# M225X.net
KiCad netlist of a schematic drawn in EAGLE
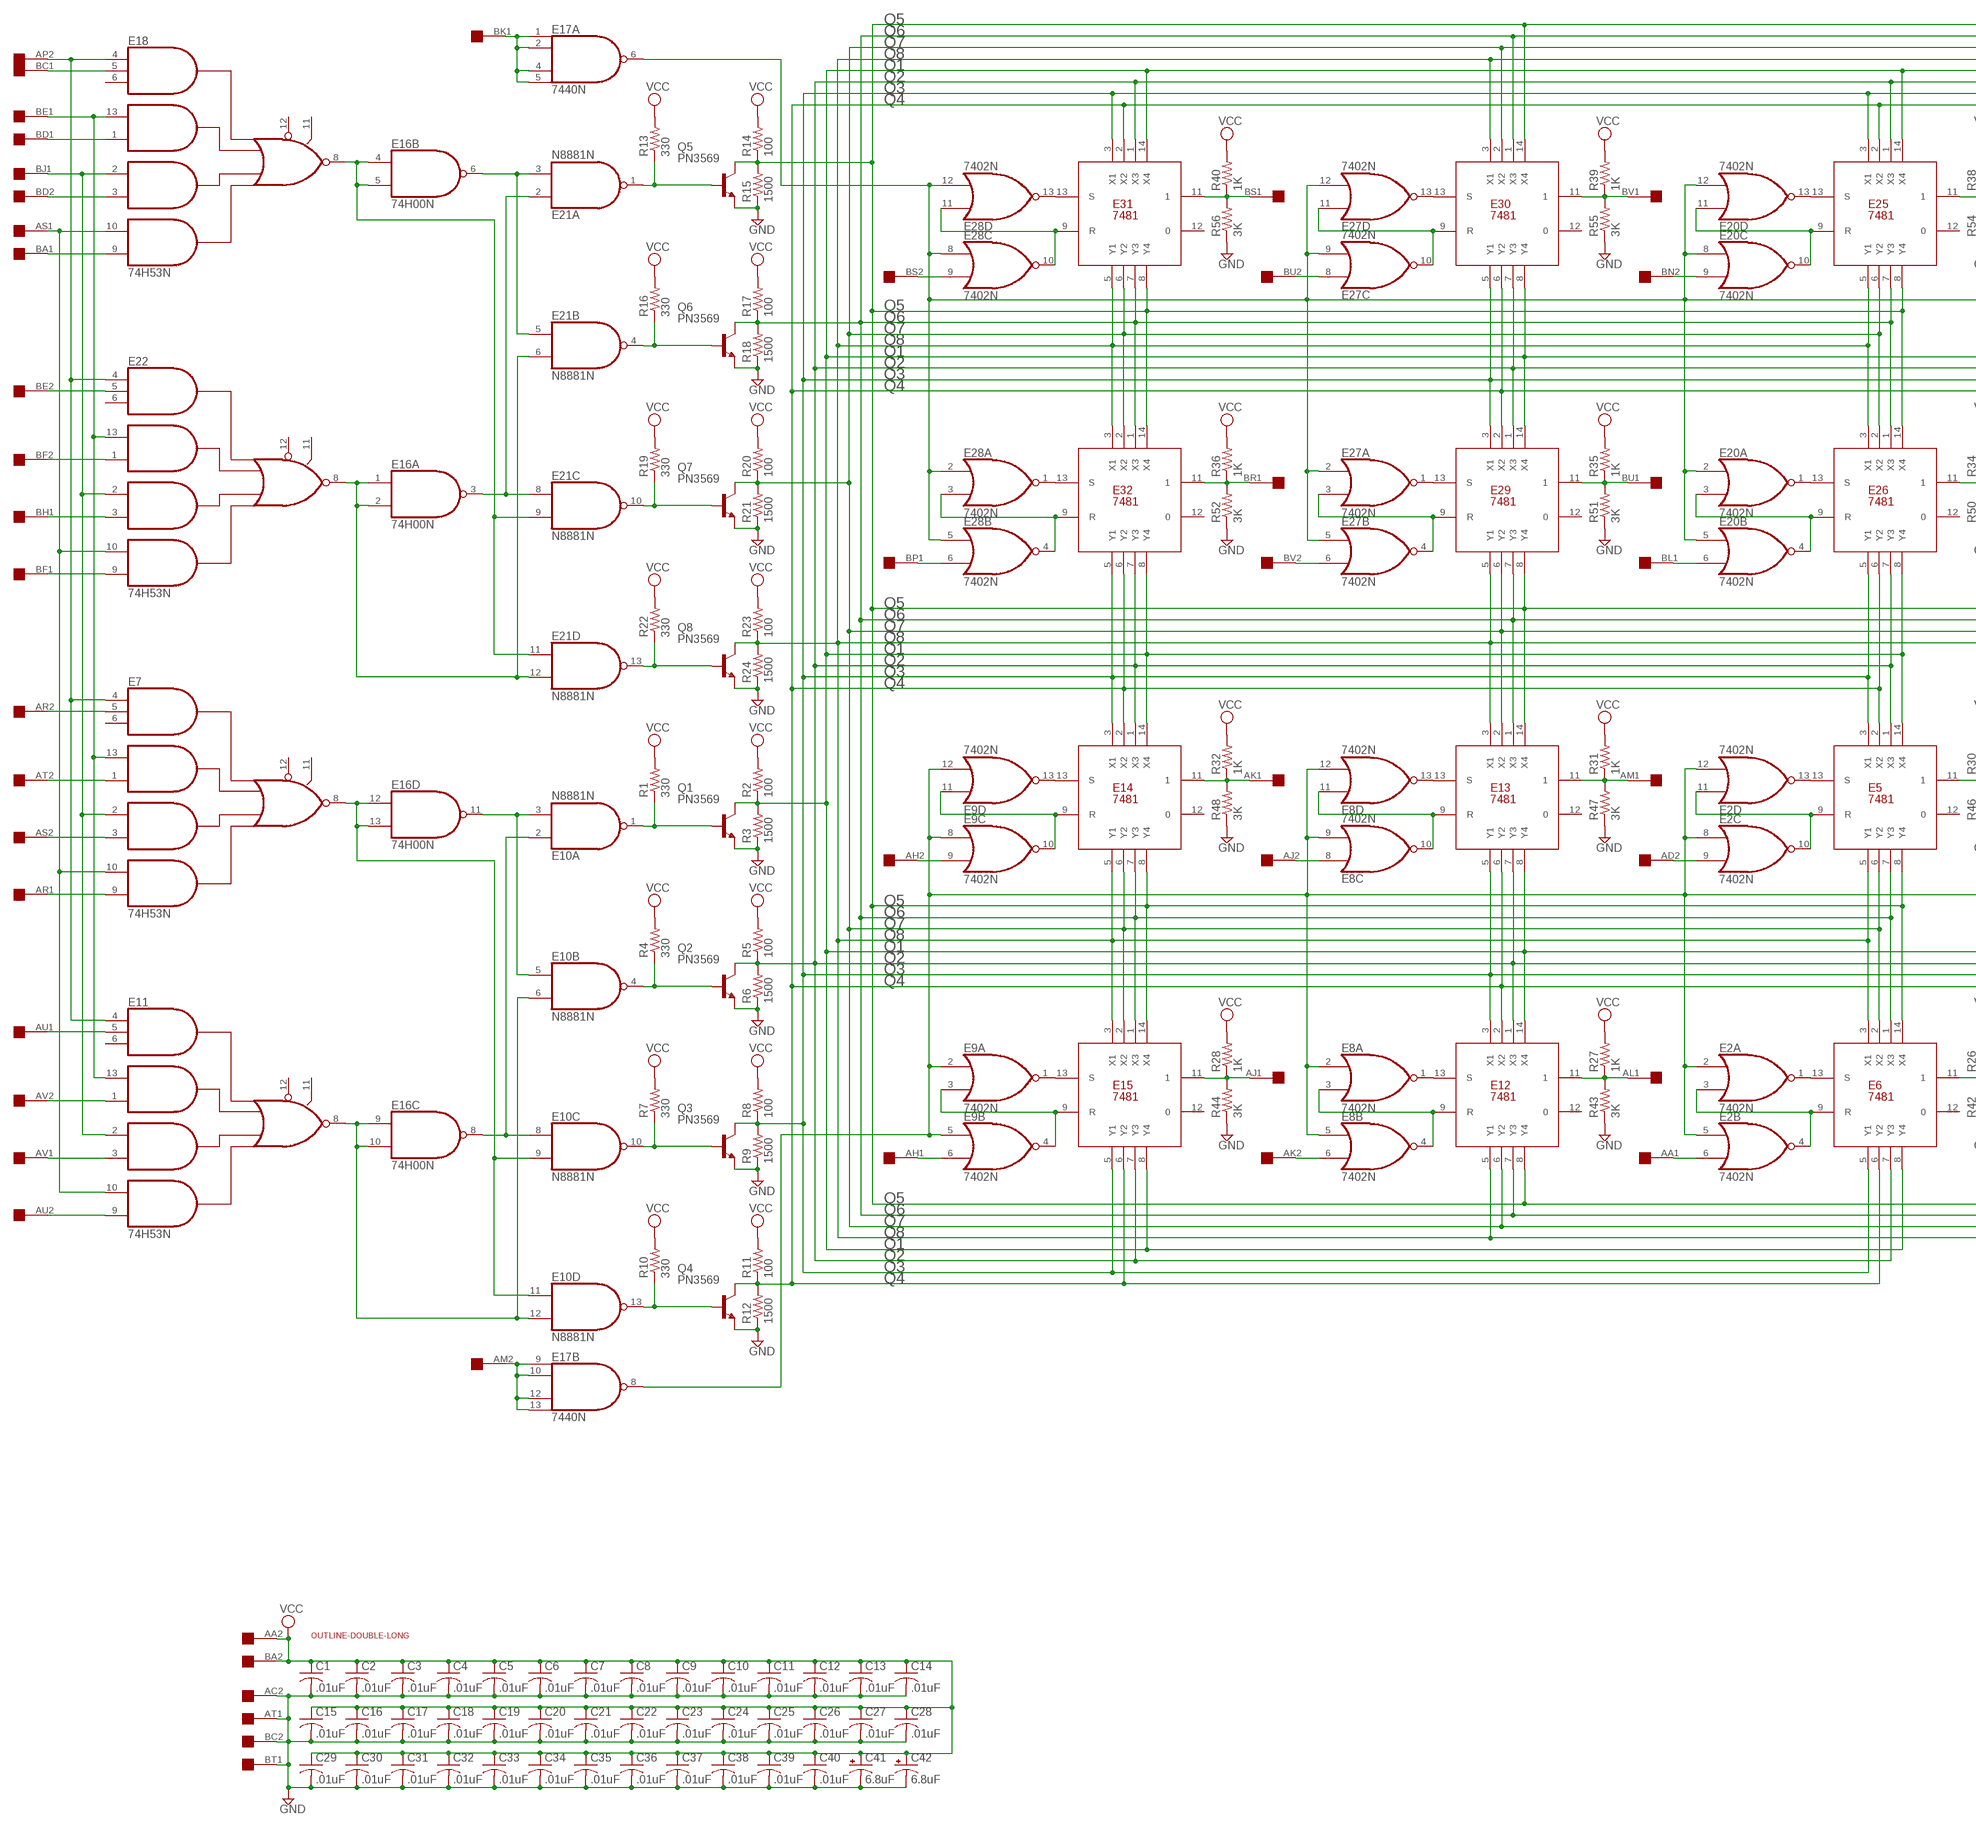
[diagram p0: schematic, sheet 1, part 1 of 2]
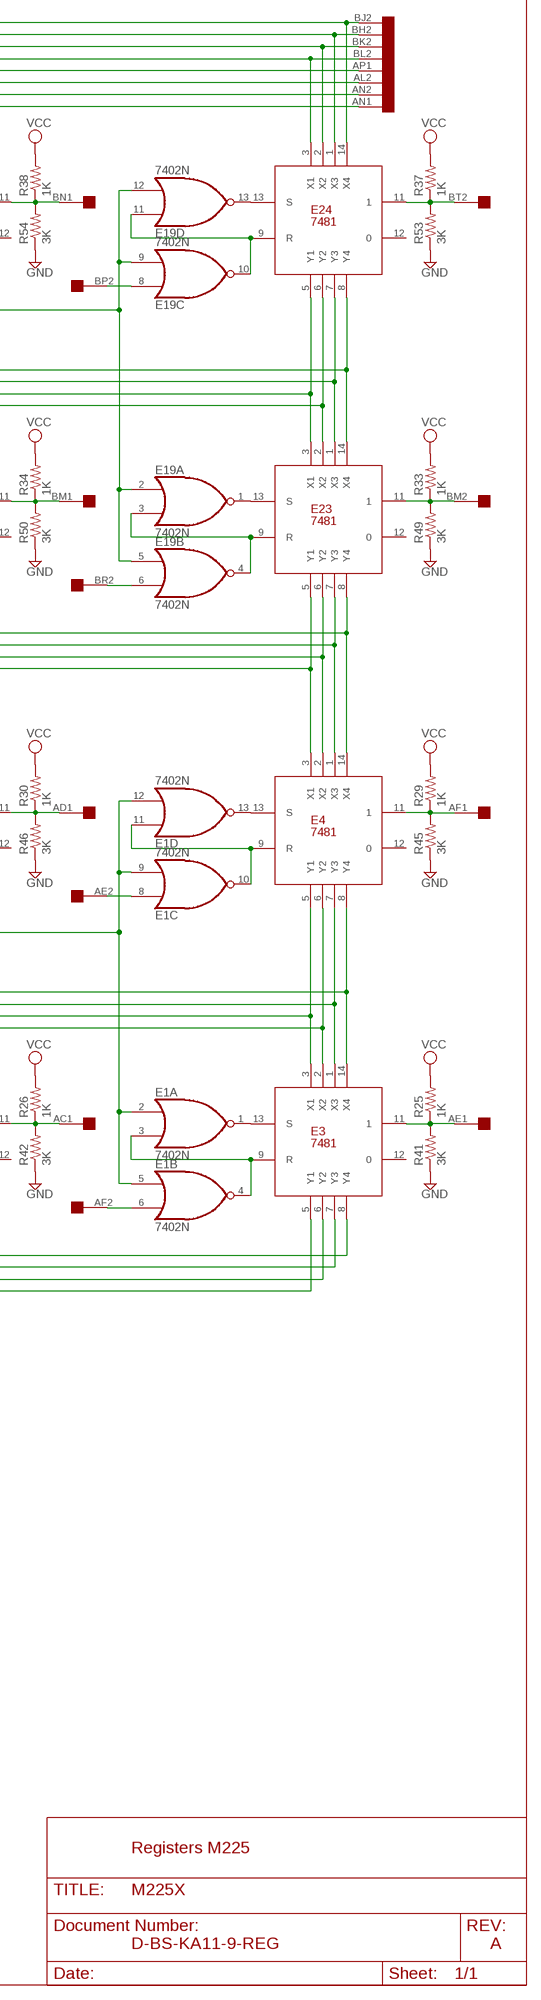
[diagram p1: schematic, sheet 1, part 2 of 2]

(export (version "E")
  (design (tool "Eeschema 10.0.6"))
  (components
    (comp (ref "C1")
      (value ".01uF")
      (footprint "eagle-import:C050-025X075")
      (libsource (lib "eagle-import") (part "C-US050-025X075"))
    )
    (comp (ref "C2")
      (value ".01uF")
      (footprint "eagle-import:C050-025X075")
      (libsource (lib "eagle-import") (part "C-US050-025X075"))
    )
    (comp (ref "C3")
      (value ".01uF")
      (footprint "eagle-import:C050-025X075")
      (libsource (lib "eagle-import") (part "C-US050-025X075"))
    )
    (comp (ref "C4")
      (value ".01uF")
      (footprint "eagle-import:C050-025X075")
      (libsource (lib "eagle-import") (part "C-US050-025X075"))
    )
    (comp (ref "C5")
      (value ".01uF")
      (footprint "eagle-import:C050-025X075")
      (libsource (lib "eagle-import") (part "C-US050-025X075"))
    )
    (comp (ref "C6")
      (value ".01uF")
      (footprint "eagle-import:C050-025X075")
      (libsource (lib "eagle-import") (part "C-US050-025X075"))
    )
    (comp (ref "C7")
      (value ".01uF")
      (footprint "eagle-import:C050-025X075")
      (libsource (lib "eagle-import") (part "C-US050-025X075"))
    )
    (comp (ref "C8")
      (value ".01uF")
      (footprint "eagle-import:C050-025X075")
      (libsource (lib "eagle-import") (part "C-US050-025X075"))
    )
    (comp (ref "C9")
      (value ".01uF")
      (footprint "eagle-import:C050-025X075")
      (libsource (lib "eagle-import") (part "C-US050-025X075"))
    )
    (comp (ref "C10")
      (value ".01uF")
      (footprint "eagle-import:C050-025X075")
      (libsource (lib "eagle-import") (part "C-US050-025X075"))
    )
    (comp (ref "C11")
      (value ".01uF")
      (footprint "eagle-import:C050-025X075")
      (libsource (lib "eagle-import") (part "C-US050-025X075"))
    )
    (comp (ref "C12")
      (value ".01uF")
      (footprint "eagle-import:C050-025X075")
      (libsource (lib "eagle-import") (part "C-US050-025X075"))
    )
    (comp (ref "C13")
      (value ".01uF")
      (footprint "eagle-import:C050-025X075")
      (libsource (lib "eagle-import") (part "C-US050-025X075"))
    )
    (comp (ref "C14")
      (value ".01uF")
      (footprint "eagle-import:C050-025X075")
      (libsource (lib "eagle-import") (part "C-US050-025X075"))
    )
    (comp (ref "C15")
      (value ".01uF")
      (footprint "eagle-import:C050-025X075")
      (libsource (lib "eagle-import") (part "C-US050-025X075"))
    )
    (comp (ref "C16")
      (value ".01uF")
      (footprint "eagle-import:C050-025X075")
      (libsource (lib "eagle-import") (part "C-US050-025X075"))
    )
    (comp (ref "C17")
      (value ".01uF")
      (footprint "eagle-import:C050-025X075")
      (libsource (lib "eagle-import") (part "C-US050-025X075"))
    )
    (comp (ref "C18")
      (value ".01uF")
      (footprint "eagle-import:C050-025X075")
      (libsource (lib "eagle-import") (part "C-US050-025X075"))
    )
    (comp (ref "C19")
      (value ".01uF")
      (footprint "eagle-import:C050-025X075")
      (libsource (lib "eagle-import") (part "C-US050-025X075"))
    )
    (comp (ref "C20")
      (value ".01uF")
      (footprint "eagle-import:C050-025X075")
      (libsource (lib "eagle-import") (part "C-US050-025X075"))
    )
    (comp (ref "C21")
      (value ".01uF")
      (footprint "eagle-import:C050-025X075")
      (libsource (lib "eagle-import") (part "C-US050-025X075"))
    )
    (comp (ref "C22")
      (value ".01uF")
      (footprint "eagle-import:C050-025X075")
      (libsource (lib "eagle-import") (part "C-US050-025X075"))
    )
    (comp (ref "C23")
      (value ".01uF")
      (footprint "eagle-import:C050-025X075")
      (libsource (lib "eagle-import") (part "C-US050-025X075"))
    )
    (comp (ref "C24")
      (value ".01uF")
      (footprint "eagle-import:C050-025X075")
      (libsource (lib "eagle-import") (part "C-US050-025X075"))
    )
    (comp (ref "C25")
      (value ".01uF")
      (footprint "eagle-import:C050-025X075")
      (libsource (lib "eagle-import") (part "C-US050-025X075"))
    )
    (comp (ref "C26")
      (value ".01uF")
      (footprint "eagle-import:C050-025X075")
      (libsource (lib "eagle-import") (part "C-US050-025X075"))
    )
    (comp (ref "C27")
      (value ".01uF")
      (footprint "eagle-import:C050-025X075")
      (libsource (lib "eagle-import") (part "C-US050-025X075"))
    )
    (comp (ref "C28")
      (value ".01uF")
      (footprint "eagle-import:C050-025X075")
      (libsource (lib "eagle-import") (part "C-US050-025X075"))
    )
    (comp (ref "C29")
      (value ".01uF")
      (footprint "eagle-import:C050-025X075")
      (libsource (lib "eagle-import") (part "C-US050-025X075"))
    )
    (comp (ref "C30")
      (value ".01uF")
      (footprint "eagle-import:C050-025X075")
      (libsource (lib "eagle-import") (part "C-US050-025X075"))
    )
    (comp (ref "C31")
      (value ".01uF")
      (footprint "eagle-import:C050-025X075")
      (libsource (lib "eagle-import") (part "C-US050-025X075"))
    )
    (comp (ref "C32")
      (value ".01uF")
      (footprint "eagle-import:C050-025X075")
      (libsource (lib "eagle-import") (part "C-US050-025X075"))
    )
    (comp (ref "C33")
      (value ".01uF")
      (footprint "eagle-import:C050-025X075")
      (libsource (lib "eagle-import") (part "C-US050-025X075"))
    )
    (comp (ref "C34")
      (value ".01uF")
      (footprint "eagle-import:C050-025X075")
      (libsource (lib "eagle-import") (part "C-US050-025X075"))
    )
    (comp (ref "C35")
      (value ".01uF")
      (footprint "eagle-import:C050-025X075")
      (libsource (lib "eagle-import") (part "C-US050-025X075"))
    )
    (comp (ref "C36")
      (value ".01uF")
      (footprint "eagle-import:C050-025X075")
      (libsource (lib "eagle-import") (part "C-US050-025X075"))
    )
    (comp (ref "C37")
      (value ".01uF")
      (footprint "eagle-import:C050-025X075")
      (libsource (lib "eagle-import") (part "C-US050-025X075"))
    )
    (comp (ref "C38")
      (value ".01uF")
      (footprint "eagle-import:C050-025X075")
      (libsource (lib "eagle-import") (part "C-US050-025X075"))
    )
    (comp (ref "C39")
      (value ".01uF")
      (footprint "eagle-import:C050-025X075")
      (libsource (lib "eagle-import") (part "C-US050-025X075"))
    )
    (comp (ref "C40")
      (value ".01uF")
      (footprint "eagle-import:C050-025X075")
      (libsource (lib "eagle-import") (part "C-US050-025X075"))
    )
    (comp (ref "C41")
      (value "6.8uF")
      (footprint "eagle-import:E12-8")
      (libsource (lib "eagle-import") (part "CPOL-USE20-8AXIAL"))
    )
    (comp (ref "C42")
      (value "6.8uF")
      (footprint "eagle-import:E12-8")
      (libsource (lib "eagle-import") (part "CPOL-USE20-8AXIAL"))
    )
    (comp (ref "E1")
      (value "7402N")
      (footprint "eagle-import:DIL14")
      (libsource (lib "eagle-import") (part "7402N"))
    )
    (comp (ref "E2")
      (value "7402N")
      (footprint "eagle-import:DIL14")
      (libsource (lib "eagle-import") (part "7402N"))
    )
    (comp (ref "E3")
      (value "7481")
      (footprint "eagle-import:DIL14")
      (libsource (lib "eagle-import") (part "7481"))
    )
    (comp (ref "E4")
      (value "7481")
      (footprint "eagle-import:DIL14")
      (libsource (lib "eagle-import") (part "7481"))
    )
    (comp (ref "E5")
      (value "7481")
      (footprint "eagle-import:DIL14")
      (libsource (lib "eagle-import") (part "7481"))
    )
    (comp (ref "E6")
      (value "7481")
      (footprint "eagle-import:DIL14")
      (libsource (lib "eagle-import") (part "7481"))
    )
    (comp (ref "E7")
      (value "74H53N")
      (footprint "eagle-import:DIL14")
      (libsource (lib "eagle-import") (part "74H53N"))
    )
    (comp (ref "E8")
      (value "7402N")
      (footprint "eagle-import:DIL14")
      (libsource (lib "eagle-import") (part "7402N"))
    )
    (comp (ref "E9")
      (value "7402N")
      (footprint "eagle-import:DIL14")
      (libsource (lib "eagle-import") (part "7402N"))
    )
    (comp (ref "E10")
      (value "N8881N")
      (footprint "eagle-import:DIL14")
      (libsource (lib "eagle-import") (part "N8881N"))
    )
    (comp (ref "E11")
      (value "74H53N")
      (footprint "eagle-import:DIL14")
      (libsource (lib "eagle-import") (part "74H53N"))
    )
    (comp (ref "E12")
      (value "7481")
      (footprint "eagle-import:DIL14")
      (libsource (lib "eagle-import") (part "7481"))
    )
    (comp (ref "E13")
      (value "7481")
      (footprint "eagle-import:DIL14")
      (libsource (lib "eagle-import") (part "7481"))
    )
    (comp (ref "E14")
      (value "7481")
      (footprint "eagle-import:DIL14")
      (libsource (lib "eagle-import") (part "7481"))
    )
    (comp (ref "E15")
      (value "7481")
      (footprint "eagle-import:DIL14")
      (libsource (lib "eagle-import") (part "7481"))
    )
    (comp (ref "E16")
      (value "74H00N")
      (footprint "eagle-import:DIL14")
      (libsource (lib "eagle-import") (part "7400NS"))
    )
    (comp (ref "E17")
      (value "7440N")
      (footprint "eagle-import:DIL14")
      (libsource (lib "eagle-import") (part "7440N"))
    )
    (comp (ref "E18")
      (value "74H53N")
      (footprint "eagle-import:DIL14")
      (libsource (lib "eagle-import") (part "74H53N"))
    )
    (comp (ref "E19")
      (value "7402N")
      (footprint "eagle-import:DIL14")
      (libsource (lib "eagle-import") (part "7402N"))
    )
    (comp (ref "E20")
      (value "7402N")
      (footprint "eagle-import:DIL14")
      (libsource (lib "eagle-import") (part "7402N"))
    )
    (comp (ref "E21")
      (value "N8881N")
      (footprint "eagle-import:DIL14")
      (libsource (lib "eagle-import") (part "N8881N"))
    )
    (comp (ref "E22")
      (value "74H53N")
      (footprint "eagle-import:DIL14")
      (libsource (lib "eagle-import") (part "74H53N"))
    )
    (comp (ref "E23")
      (value "7481")
      (footprint "eagle-import:DIL14")
      (libsource (lib "eagle-import") (part "7481"))
    )
    (comp (ref "E24")
      (value "7481")
      (footprint "eagle-import:DIL14")
      (libsource (lib "eagle-import") (part "7481"))
    )
    (comp (ref "E25")
      (value "7481")
      (footprint "eagle-import:DIL14")
      (libsource (lib "eagle-import") (part "7481"))
    )
    (comp (ref "E26")
      (value "7481")
      (footprint "eagle-import:DIL14")
      (libsource (lib "eagle-import") (part "7481"))
    )
    (comp (ref "E27")
      (value "7402N")
      (footprint "eagle-import:DIL14")
      (libsource (lib "eagle-import") (part "7402N"))
    )
    (comp (ref "E28")
      (value "7402N")
      (footprint "eagle-import:DIL14")
      (libsource (lib "eagle-import") (part "7402N"))
    )
    (comp (ref "E29")
      (value "7481")
      (footprint "eagle-import:DIL14")
      (libsource (lib "eagle-import") (part "7481"))
    )
    (comp (ref "E30")
      (value "7481")
      (footprint "eagle-import:DIL14")
      (libsource (lib "eagle-import") (part "7481"))
    )
    (comp (ref "E31")
      (value "7481")
      (footprint "eagle-import:DIL14")
      (libsource (lib "eagle-import") (part "7481"))
    )
    (comp (ref "E32")
      (value "7481")
      (footprint "eagle-import:DIL14")
      (libsource (lib "eagle-import") (part "7481"))
    )
    (comp (ref "Q1")
      (value "PN3569")
      (footprint "eagle-import:TO5")
      (libsource (lib "eagle-import") (part "-NPN-TO5"))
    )
    (comp (ref "Q2")
      (value "PN3569")
      (footprint "eagle-import:TO5")
      (libsource (lib "eagle-import") (part "-NPN-TO5"))
    )
    (comp (ref "Q3")
      (value "PN3569")
      (footprint "eagle-import:TO5")
      (libsource (lib "eagle-import") (part "-NPN-TO5"))
    )
    (comp (ref "Q4")
      (value "PN3569")
      (footprint "eagle-import:TO5")
      (libsource (lib "eagle-import") (part "-NPN-TO5"))
    )
    (comp (ref "Q5")
      (value "PN3569")
      (footprint "eagle-import:TO5")
      (libsource (lib "eagle-import") (part "-NPN-TO5"))
    )
    (comp (ref "Q6")
      (value "PN3569")
      (footprint "eagle-import:TO5")
      (libsource (lib "eagle-import") (part "-NPN-TO5"))
    )
    (comp (ref "Q7")
      (value "PN3569")
      (footprint "eagle-import:TO5")
      (libsource (lib "eagle-import") (part "-NPN-TO5"))
    )
    (comp (ref "Q8")
      (value "PN3569")
      (footprint "eagle-import:TO5")
      (libsource (lib "eagle-import") (part "-NPN-TO5"))
    )
    (comp (ref "R1")
      (value "330")
      (footprint "eagle-import:0207_10")
      (libsource (lib "eagle-import") (part "R-US_0207/10"))
    )
    (comp (ref "R2")
      (value "100")
      (footprint "eagle-import:0207_10")
      (libsource (lib "eagle-import") (part "R-US_0207/10"))
    )
    (comp (ref "R3")
      (value "1500")
      (footprint "eagle-import:0207_10")
      (libsource (lib "eagle-import") (part "R-US_0207/10"))
    )
    (comp (ref "R4")
      (value "330")
      (footprint "eagle-import:0207_10")
      (libsource (lib "eagle-import") (part "R-US_0207/10"))
    )
    (comp (ref "R5")
      (value "100")
      (footprint "eagle-import:0207_10")
      (libsource (lib "eagle-import") (part "R-US_0207/10"))
    )
    (comp (ref "R6")
      (value "1500")
      (footprint "eagle-import:0207_10")
      (libsource (lib "eagle-import") (part "R-US_0207/10"))
    )
    (comp (ref "R7")
      (value "330")
      (footprint "eagle-import:0207_10")
      (libsource (lib "eagle-import") (part "R-US_0207/10"))
    )
    (comp (ref "R8")
      (value "100")
      (footprint "eagle-import:0207_10")
      (libsource (lib "eagle-import") (part "R-US_0207/10"))
    )
    (comp (ref "R9")
      (value "1500")
      (footprint "eagle-import:0207_10")
      (libsource (lib "eagle-import") (part "R-US_0207/10"))
    )
    (comp (ref "R10")
      (value "330")
      (footprint "eagle-import:0207_10")
      (libsource (lib "eagle-import") (part "R-US_0207/10"))
    )
    (comp (ref "R11")
      (value "100")
      (footprint "eagle-import:0207_10")
      (libsource (lib "eagle-import") (part "R-US_0207/10"))
    )
    (comp (ref "R12")
      (value "1500")
      (footprint "eagle-import:0207_10")
      (libsource (lib "eagle-import") (part "R-US_0207/10"))
    )
    (comp (ref "R13")
      (value "330")
      (footprint "eagle-import:0207_10")
      (libsource (lib "eagle-import") (part "R-US_0207/10"))
    )
    (comp (ref "R14")
      (value "100")
      (footprint "eagle-import:0207_10")
      (libsource (lib "eagle-import") (part "R-US_0207/10"))
    )
    (comp (ref "R15")
      (value "1500")
      (footprint "eagle-import:0207_10")
      (libsource (lib "eagle-import") (part "R-US_0207/10"))
    )
    (comp (ref "R16")
      (value "330")
      (footprint "eagle-import:0207_10")
      (libsource (lib "eagle-import") (part "R-US_0207/10"))
    )
    (comp (ref "R17")
      (value "100")
      (footprint "eagle-import:0207_10")
      (libsource (lib "eagle-import") (part "R-US_0207/10"))
    )
    (comp (ref "R18")
      (value "1500")
      (footprint "eagle-import:0207_10")
      (libsource (lib "eagle-import") (part "R-US_0207/10"))
    )
    (comp (ref "R19")
      (value "330")
      (footprint "eagle-import:0207_10")
      (libsource (lib "eagle-import") (part "R-US_0207/10"))
    )
    (comp (ref "R20")
      (value "100")
      (footprint "eagle-import:0207_10")
      (libsource (lib "eagle-import") (part "R-US_0207/10"))
    )
    (comp (ref "R21")
      (value "1500")
      (footprint "eagle-import:0207_10")
      (libsource (lib "eagle-import") (part "R-US_0207/10"))
    )
    (comp (ref "R22")
      (value "330")
      (footprint "eagle-import:0207_10")
      (libsource (lib "eagle-import") (part "R-US_0207/10"))
    )
    (comp (ref "R23")
      (value "100")
      (footprint "eagle-import:0207_10")
      (libsource (lib "eagle-import") (part "R-US_0207/10"))
    )
    (comp (ref "R24")
      (value "1500")
      (footprint "eagle-import:0207_10")
      (libsource (lib "eagle-import") (part "R-US_0207/10"))
    )
    (comp (ref "R25")
      (value "1K")
      (footprint "eagle-import:0207_10")
      (libsource (lib "eagle-import") (part "R-US_0207/10"))
    )
    (comp (ref "R26")
      (value "1K")
      (footprint "eagle-import:0207_10")
      (libsource (lib "eagle-import") (part "R-US_0207/10"))
    )
    (comp (ref "R27")
      (value "1K")
      (footprint "eagle-import:0207_10")
      (libsource (lib "eagle-import") (part "R-US_0207/10"))
    )
    (comp (ref "R28")
      (value "1K")
      (footprint "eagle-import:0207_10")
      (libsource (lib "eagle-import") (part "R-US_0207/10"))
    )
    (comp (ref "R29")
      (value "1K")
      (footprint "eagle-import:0207_10")
      (libsource (lib "eagle-import") (part "R-US_0207/10"))
    )
    (comp (ref "R30")
      (value "1K")
      (footprint "eagle-import:0207_10")
      (libsource (lib "eagle-import") (part "R-US_0207/10"))
    )
    (comp (ref "R31")
      (value "1K")
      (footprint "eagle-import:0207_10")
      (libsource (lib "eagle-import") (part "R-US_0207/10"))
    )
    (comp (ref "R32")
      (value "1K")
      (footprint "eagle-import:0207_10")
      (libsource (lib "eagle-import") (part "R-US_0207/10"))
    )
    (comp (ref "R33")
      (value "1K")
      (footprint "eagle-import:0207_10")
      (libsource (lib "eagle-import") (part "R-US_0207/10"))
    )
    (comp (ref "R34")
      (value "1K")
      (footprint "eagle-import:0207_10")
      (libsource (lib "eagle-import") (part "R-US_0207/10"))
    )
    (comp (ref "R35")
      (value "1K")
      (footprint "eagle-import:0207_10")
      (libsource (lib "eagle-import") (part "R-US_0207/10"))
    )
    (comp (ref "R36")
      (value "1K")
      (footprint "eagle-import:0207_10")
      (libsource (lib "eagle-import") (part "R-US_0207/10"))
    )
    (comp (ref "R37")
      (value "1K")
      (footprint "eagle-import:0207_10")
      (libsource (lib "eagle-import") (part "R-US_0207/10"))
    )
    (comp (ref "R38")
      (value "1K")
      (footprint "eagle-import:0207_10")
      (libsource (lib "eagle-import") (part "R-US_0207/10"))
    )
    (comp (ref "R39")
      (value "1K")
      (footprint "eagle-import:0207_10")
      (libsource (lib "eagle-import") (part "R-US_0207/10"))
    )
    (comp (ref "R40")
      (value "1K")
      (footprint "eagle-import:0207_10")
      (libsource (lib "eagle-import") (part "R-US_0207/10"))
    )
    (comp (ref "R41")
      (value "3K")
      (footprint "eagle-import:0207_10")
      (libsource (lib "eagle-import") (part "R-US_0207/10"))
    )
    (comp (ref "R42")
      (value "3K")
      (footprint "eagle-import:0207_10")
      (libsource (lib "eagle-import") (part "R-US_0207/10"))
    )
    (comp (ref "R43")
      (value "3K")
      (footprint "eagle-import:0207_10")
      (libsource (lib "eagle-import") (part "R-US_0207/10"))
    )
    (comp (ref "R44")
      (value "3K")
      (footprint "eagle-import:0207_10")
      (libsource (lib "eagle-import") (part "R-US_0207/10"))
    )
    (comp (ref "R45")
      (value "3K")
      (footprint "eagle-import:0207_10")
      (libsource (lib "eagle-import") (part "R-US_0207/10"))
    )
    (comp (ref "R46")
      (value "3K")
      (footprint "eagle-import:0207_10")
      (libsource (lib "eagle-import") (part "R-US_0207/10"))
    )
    (comp (ref "R47")
      (value "3K")
      (footprint "eagle-import:0207_10")
      (libsource (lib "eagle-import") (part "R-US_0207/10"))
    )
    (comp (ref "R48")
      (value "3K")
      (footprint "eagle-import:0207_10")
      (libsource (lib "eagle-import") (part "R-US_0207/10"))
    )
    (comp (ref "R49")
      (value "3K")
      (footprint "eagle-import:0207_10")
      (libsource (lib "eagle-import") (part "R-US_0207/10"))
    )
    (comp (ref "R50")
      (value "3K")
      (footprint "eagle-import:0207_10")
      (libsource (lib "eagle-import") (part "R-US_0207/10"))
    )
    (comp (ref "R51")
      (value "3K")
      (footprint "eagle-import:0207_10")
      (libsource (lib "eagle-import") (part "R-US_0207/10"))
    )
    (comp (ref "R52")
      (value "3K")
      (footprint "eagle-import:0207_10")
      (libsource (lib "eagle-import") (part "R-US_0207/10"))
    )
    (comp (ref "R53")
      (value "3K")
      (footprint "eagle-import:0207_10")
      (libsource (lib "eagle-import") (part "R-US_0207/10"))
    )
    (comp (ref "R54")
      (value "3K")
      (footprint "eagle-import:0207_10")
      (libsource (lib "eagle-import") (part "R-US_0207/10"))
    )
    (comp (ref "R55")
      (value "3K")
      (footprint "eagle-import:0207_10")
      (libsource (lib "eagle-import") (part "R-US_0207/10"))
    )
    (comp (ref "R56")
      (value "3K")
      (footprint "eagle-import:0207_10")
      (libsource (lib "eagle-import") (part "R-US_0207/10"))
    )
    (comp (ref "U$1")
      (value "OUTLINE-DOUBLE-LONG")
      (footprint "eagle-import:DOUBLE-LONG")
      (libsource (lib "eagle-import") (part "OUTLINE-DOUBLE-LONG"))
    )
    (comp (ref "U$3")
      (value "DOUBLE")
      (footprint "eagle-import:EDGE-CON4")
      (libsource (lib "eagle-import") (part "DOUBLE"))
    )
  )
  (nets
    (net (code "1") (name "/Q1") (class "Default")
      (node (ref "E12") (pin "14") (pinfunction "X4_14") (pintype "input"))
      (node (ref "E13") (pin "8") (pinfunction "Y4_8") (pintype "input"))
      (node (ref "E14") (pin "14") (pinfunction "X4_14") (pintype "input"))
      (node (ref "E15") (pin "8") (pinfunction "Y4_8") (pintype "input"))
      (node (ref "E23") (pin "14") (pinfunction "X4_14") (pintype "input"))
      (node (ref "E24") (pin "8") (pinfunction "Y4_8") (pintype "input"))
      (node (ref "E25") (pin "14") (pinfunction "X4_14") (pintype "input"))
      (node (ref "E26") (pin "8") (pinfunction "Y4_8") (pintype "input"))
      (node (ref "E29") (pin "14") (pinfunction "X4_14") (pintype "input"))
      (node (ref "E3") (pin "14") (pinfunction "X4_14") (pintype "input"))
      (node (ref "E30") (pin "8") (pinfunction "Y4_8") (pintype "input"))
      (node (ref "E31") (pin "14") (pinfunction "X4_14") (pintype "input"))
      (node (ref "E32") (pin "8") (pinfunction "Y4_8") (pintype "input"))
      (node (ref "E4") (pin "8") (pinfunction "Y4_8") (pintype "input"))
      (node (ref "E5") (pin "14") (pinfunction "X4_14") (pintype "input"))
      (node (ref "E6") (pin "8") (pinfunction "Y4_8") (pintype "input"))
      (node (ref "Q1") (pin "3") (pinfunction "C_3") (pintype "passive"))
      (node (ref "R2") (pin "1") (pinfunction "1_1") (pintype "passive"))
      (node (ref "R3") (pin "2") (pinfunction "2_2") (pintype "passive"))
      (node (ref "U$3") (pin "AP1") (pinfunction "1_AP1") (pintype "bidirectional"))
    )
    (net (code "2") (name "/Q2") (class "Default")
      (node (ref "E12") (pin "1") (pinfunction "X3_1") (pintype "input"))
      (node (ref "E13") (pin "7") (pinfunction "Y3_7") (pintype "input"))
      (node (ref "E14") (pin "1") (pinfunction "X3_1") (pintype "input"))
      (node (ref "E15") (pin "7") (pinfunction "Y3_7") (pintype "input"))
      (node (ref "E23") (pin "1") (pinfunction "X3_1") (pintype "input"))
      (node (ref "E24") (pin "7") (pinfunction "Y3_7") (pintype "input"))
      (node (ref "E25") (pin "1") (pinfunction "X3_1") (pintype "input"))
      (node (ref "E26") (pin "7") (pinfunction "Y3_7") (pintype "input"))
      (node (ref "E29") (pin "1") (pinfunction "X3_1") (pintype "input"))
      (node (ref "E3") (pin "1") (pinfunction "X3_1") (pintype "input"))
      (node (ref "E30") (pin "7") (pinfunction "Y3_7") (pintype "input"))
      (node (ref "E31") (pin "1") (pinfunction "X3_1") (pintype "input"))
      (node (ref "E32") (pin "7") (pinfunction "Y3_7") (pintype "input"))
      (node (ref "E4") (pin "7") (pinfunction "Y3_7") (pintype "input"))
      (node (ref "E5") (pin "1") (pinfunction "X3_1") (pintype "input"))
      (node (ref "E6") (pin "7") (pinfunction "Y3_7") (pintype "input"))
      (node (ref "Q2") (pin "3") (pinfunction "C_3") (pintype "passive"))
      (node (ref "R5") (pin "1") (pinfunction "1_1") (pintype "passive"))
      (node (ref "R6") (pin "2") (pinfunction "2_2") (pintype "passive"))
      (node (ref "U$3") (pin "AL2") (pinfunction "1_AL2") (pintype "bidirectional"))
    )
    (net (code "3") (name "/Q3") (class "Default")
      (node (ref "E12") (pin "3") (pinfunction "X1_3") (pintype "input"))
      (node (ref "E13") (pin "5") (pinfunction "Y1_5") (pintype "input"))
      (node (ref "E14") (pin "3") (pinfunction "X1_3") (pintype "input"))
      (node (ref "E15") (pin "5") (pinfunction "Y1_5") (pintype "input"))
      (node (ref "E23") (pin "3") (pinfunction "X1_3") (pintype "input"))
      (node (ref "E24") (pin "5") (pinfunction "Y1_5") (pintype "input"))
      (node (ref "E25") (pin "3") (pinfunction "X1_3") (pintype "input"))
      (node (ref "E26") (pin "5") (pinfunction "Y1_5") (pintype "input"))
      (node (ref "E29") (pin "3") (pinfunction "X1_3") (pintype "input"))
      (node (ref "E3") (pin "3") (pinfunction "X1_3") (pintype "input"))
      (node (ref "E30") (pin "5") (pinfunction "Y1_5") (pintype "input"))
      (node (ref "E31") (pin "3") (pinfunction "X1_3") (pintype "input"))
      (node (ref "E32") (pin "5") (pinfunction "Y1_5") (pintype "input"))
      (node (ref "E4") (pin "5") (pinfunction "Y1_5") (pintype "input"))
      (node (ref "E5") (pin "3") (pinfunction "X1_3") (pintype "input"))
      (node (ref "E6") (pin "5") (pinfunction "Y1_5") (pintype "input"))
      (node (ref "Q3") (pin "3") (pinfunction "C_3") (pintype "passive"))
      (node (ref "R8") (pin "1") (pinfunction "1_1") (pintype "passive"))
      (node (ref "R9") (pin "2") (pinfunction "2_2") (pintype "passive"))
      (node (ref "U$3") (pin "AN2") (pinfunction "1_AN2") (pintype "bidirectional"))
    )
    (net (code "4") (name "/Q4") (class "Default")
      (node (ref "E12") (pin "2") (pinfunction "X2_2") (pintype "input"))
      (node (ref "E13") (pin "6") (pinfunction "Y2_6") (pintype "input"))
      (node (ref "E14") (pin "2") (pinfunction "X2_2") (pintype "input"))
      (node (ref "E15") (pin "6") (pinfunction "Y2_6") (pintype "input"))
      (node (ref "E23") (pin "2") (pinfunction "X2_2") (pintype "input"))
      (node (ref "E24") (pin "6") (pinfunction "Y2_6") (pintype "input"))
      (node (ref "E25") (pin "2") (pinfunction "X2_2") (pintype "input"))
      (node (ref "E26") (pin "6") (pinfunction "Y2_6") (pintype "input"))
      (node (ref "E29") (pin "2") (pinfunction "X2_2") (pintype "input"))
      (node (ref "E3") (pin "2") (pinfunction "X2_2") (pintype "input"))
      (node (ref "E30") (pin "6") (pinfunction "Y2_6") (pintype "input"))
      (node (ref "E31") (pin "2") (pinfunction "X2_2") (pintype "input"))
      (node (ref "E32") (pin "6") (pinfunction "Y2_6") (pintype "input"))
      (node (ref "E4") (pin "6") (pinfunction "Y2_6") (pintype "input"))
      (node (ref "E5") (pin "2") (pinfunction "X2_2") (pintype "input"))
      (node (ref "E6") (pin "6") (pinfunction "Y2_6") (pintype "input"))
      (node (ref "Q4") (pin "3") (pinfunction "C_3") (pintype "passive"))
      (node (ref "R11") (pin "1") (pinfunction "1_1") (pintype "passive"))
      (node (ref "R12") (pin "2") (pinfunction "2_2") (pintype "passive"))
      (node (ref "U$3") (pin "AN1") (pinfunction "1_AN1") (pintype "bidirectional"))
    )
    (net (code "5") (name "/Q5") (class "Default")
      (node (ref "E12") (pin "8") (pinfunction "Y4_8") (pintype "input"))
      (node (ref "E13") (pin "14") (pinfunction "X4_14") (pintype "input"))
      (node (ref "E14") (pin "8") (pinfunction "Y4_8") (pintype "input"))
      (node (ref "E15") (pin "14") (pinfunction "X4_14") (pintype "input"))
      (node (ref "E23") (pin "8") (pinfunction "Y4_8") (pintype "input"))
      (node (ref "E24") (pin "14") (pinfunction "X4_14") (pintype "input"))
      (node (ref "E25") (pin "8") (pinfunction "Y4_8") (pintype "input"))
      (node (ref "E26") (pin "14") (pinfunction "X4_14") (pintype "input"))
      (node (ref "E29") (pin "8") (pinfunction "Y4_8") (pintype "input"))
      (node (ref "E3") (pin "8") (pinfunction "Y4_8") (pintype "input"))
      (node (ref "E30") (pin "14") (pinfunction "X4_14") (pintype "input"))
      (node (ref "E31") (pin "8") (pinfunction "Y4_8") (pintype "input"))
      (node (ref "E32") (pin "14") (pinfunction "X4_14") (pintype "input"))
      (node (ref "E4") (pin "14") (pinfunction "X4_14") (pintype "input"))
      (node (ref "E5") (pin "8") (pinfunction "Y4_8") (pintype "input"))
      (node (ref "E6") (pin "14") (pinfunction "X4_14") (pintype "input"))
      (node (ref "Q5") (pin "3") (pinfunction "C_3") (pintype "passive"))
      (node (ref "R14") (pin "1") (pinfunction "1_1") (pintype "passive"))
      (node (ref "R15") (pin "2") (pinfunction "2_2") (pintype "passive"))
      (node (ref "U$3") (pin "BJ2") (pinfunction "1_BJ2") (pintype "bidirectional"))
    )
    (net (code "6") (name "/Q6") (class "Default")
      (node (ref "E12") (pin "7") (pinfunction "Y3_7") (pintype "input"))
      (node (ref "E13") (pin "1") (pinfunction "X3_1") (pintype "input"))
      (node (ref "E14") (pin "7") (pinfunction "Y3_7") (pintype "input"))
      (node (ref "E15") (pin "1") (pinfunction "X3_1") (pintype "input"))
      (node (ref "E23") (pin "7") (pinfunction "Y3_7") (pintype "input"))
      (node (ref "E24") (pin "1") (pinfunction "X3_1") (pintype "input"))
      (node (ref "E25") (pin "7") (pinfunction "Y3_7") (pintype "input"))
      (node (ref "E26") (pin "1") (pinfunction "X3_1") (pintype "input"))
      (node (ref "E29") (pin "7") (pinfunction "Y3_7") (pintype "input"))
      (node (ref "E3") (pin "7") (pinfunction "Y3_7") (pintype "input"))
      (node (ref "E30") (pin "1") (pinfunction "X3_1") (pintype "input"))
      (node (ref "E31") (pin "7") (pinfunction "Y3_7") (pintype "input"))
      (node (ref "E32") (pin "1") (pinfunction "X3_1") (pintype "input"))
      (node (ref "E4") (pin "1") (pinfunction "X3_1") (pintype "input"))
      (node (ref "E5") (pin "7") (pinfunction "Y3_7") (pintype "input"))
      (node (ref "E6") (pin "1") (pinfunction "X3_1") (pintype "input"))
      (node (ref "Q6") (pin "3") (pinfunction "C_3") (pintype "passive"))
      (node (ref "R17") (pin "1") (pinfunction "1_1") (pintype "passive"))
      (node (ref "R18") (pin "2") (pinfunction "2_2") (pintype "passive"))
      (node (ref "U$3") (pin "BH2") (pinfunction "1_BH2") (pintype "bidirectional"))
    )
    (net (code "7") (name "/Q7") (class "Default")
      (node (ref "E12") (pin "6") (pinfunction "Y2_6") (pintype "input"))
      (node (ref "E13") (pin "2") (pinfunction "X2_2") (pintype "input"))
      (node (ref "E14") (pin "6") (pinfunction "Y2_6") (pintype "input"))
      (node (ref "E15") (pin "2") (pinfunction "X2_2") (pintype "input"))
      (node (ref "E23") (pin "6") (pinfunction "Y2_6") (pintype "input"))
      (node (ref "E24") (pin "2") (pinfunction "X2_2") (pintype "input"))
      (node (ref "E25") (pin "6") (pinfunction "Y2_6") (pintype "input"))
      (node (ref "E26") (pin "2") (pinfunction "X2_2") (pintype "input"))
      (node (ref "E29") (pin "6") (pinfunction "Y2_6") (pintype "input"))
      (node (ref "E3") (pin "6") (pinfunction "Y2_6") (pintype "input"))
      (node (ref "E30") (pin "2") (pinfunction "X2_2") (pintype "input"))
      (node (ref "E31") (pin "6") (pinfunction "Y2_6") (pintype "input"))
      (node (ref "E32") (pin "2") (pinfunction "X2_2") (pintype "input"))
      (node (ref "E4") (pin "2") (pinfunction "X2_2") (pintype "input"))
      (node (ref "E5") (pin "6") (pinfunction "Y2_6") (pintype "input"))
      (node (ref "E6") (pin "2") (pinfunction "X2_2") (pintype "input"))
      (node (ref "Q7") (pin "3") (pinfunction "C_3") (pintype "passive"))
      (node (ref "R20") (pin "1") (pinfunction "1_1") (pintype "passive"))
      (node (ref "R21") (pin "2") (pinfunction "2_2") (pintype "passive"))
      (node (ref "U$3") (pin "BK2") (pinfunction "1_BK2") (pintype "bidirectional"))
    )
    (net (code "8") (name "/Q8") (class "Default")
      (node (ref "E12") (pin "5") (pinfunction "Y1_5") (pintype "input"))
      (node (ref "E13") (pin "3") (pinfunction "X1_3") (pintype "input"))
      (node (ref "E14") (pin "5") (pinfunction "Y1_5") (pintype "input"))
      (node (ref "E15") (pin "3") (pinfunction "X1_3") (pintype "input"))
      (node (ref "E23") (pin "5") (pinfunction "Y1_5") (pintype "input"))
      (node (ref "E24") (pin "3") (pinfunction "X1_3") (pintype "input"))
      (node (ref "E25") (pin "5") (pinfunction "Y1_5") (pintype "input"))
      (node (ref "E26") (pin "3") (pinfunction "X1_3") (pintype "input"))
      (node (ref "E29") (pin "5") (pinfunction "Y1_5") (pintype "input"))
      (node (ref "E3") (pin "5") (pinfunction "Y1_5") (pintype "input"))
      (node (ref "E30") (pin "3") (pinfunction "X1_3") (pintype "input"))
      (node (ref "E31") (pin "5") (pinfunction "Y1_5") (pintype "input"))
      (node (ref "E32") (pin "3") (pinfunction "X1_3") (pintype "input"))
      (node (ref "E4") (pin "3") (pinfunction "X1_3") (pintype "input"))
      (node (ref "E5") (pin "5") (pinfunction "Y1_5") (pintype "input"))
      (node (ref "E6") (pin "3") (pinfunction "X1_3") (pintype "input"))
      (node (ref "Q8") (pin "3") (pinfunction "C_3") (pintype "passive"))
      (node (ref "R23") (pin "1") (pinfunction "1_1") (pintype "passive"))
      (node (ref "R24") (pin "2") (pinfunction "2_2") (pintype "passive"))
      (node (ref "U$3") (pin "BL2") (pinfunction "1_BL2") (pintype "bidirectional"))
    )
    (net (code "9") (name "GND") (class "Default")
      (node (ref "C1") (pin "2") (pinfunction "2_2") (pintype "passive"))
      (node (ref "C10") (pin "2") (pinfunction "2_2") (pintype "passive"))
      (node (ref "C11") (pin "2") (pinfunction "2_2") (pintype "passive"))
      (node (ref "C12") (pin "2") (pinfunction "2_2") (pintype "passive"))
      (node (ref "C13") (pin "2") (pinfunction "2_2") (pintype "passive"))
      (node (ref "C14") (pin "2") (pinfunction "2_2") (pintype "passive"))
      (node (ref "C15") (pin "2") (pinfunction "2_2") (pintype "passive"))
      (node (ref "C16") (pin "2") (pinfunction "2_2") (pintype "passive"))
      (node (ref "C17") (pin "2") (pinfunction "2_2") (pintype "passive"))
      (node (ref "C18") (pin "2") (pinfunction "2_2") (pintype "passive"))
      (node (ref "C19") (pin "2") (pinfunction "2_2") (pintype "passive"))
      (node (ref "C2") (pin "2") (pinfunction "2_2") (pintype "passive"))
      (node (ref "C20") (pin "2") (pinfunction "2_2") (pintype "passive"))
      (node (ref "C21") (pin "2") (pinfunction "2_2") (pintype "passive"))
      (node (ref "C22") (pin "2") (pinfunction "2_2") (pintype "passive"))
      (node (ref "C23") (pin "2") (pinfunction "2_2") (pintype "passive"))
      (node (ref "C24") (pin "2") (pinfunction "2_2") (pintype "passive"))
      (node (ref "C25") (pin "2") (pinfunction "2_2") (pintype "passive"))
      (node (ref "C26") (pin "2") (pinfunction "2_2") (pintype "passive"))
      (node (ref "C27") (pin "2") (pinfunction "2_2") (pintype "passive"))
      (node (ref "C28") (pin "2") (pinfunction "2_2") (pintype "passive"))
      (node (ref "C29") (pin "2") (pinfunction "2_2") (pintype "passive"))
      (node (ref "C3") (pin "2") (pinfunction "2_2") (pintype "passive"))
      (node (ref "C30") (pin "2") (pinfunction "2_2") (pintype "passive"))
      (node (ref "C31") (pin "2") (pinfunction "2_2") (pintype "passive"))
      (node (ref "C32") (pin "2") (pinfunction "2_2") (pintype "passive"))
      (node (ref "C33") (pin "2") (pinfunction "2_2") (pintype "passive"))
      (node (ref "C34") (pin "2") (pinfunction "2_2") (pintype "passive"))
      (node (ref "C35") (pin "2") (pinfunction "2_2") (pintype "passive"))
      (node (ref "C36") (pin "2") (pinfunction "2_2") (pintype "passive"))
      (node (ref "C37") (pin "2") (pinfunction "2_2") (pintype "passive"))
      (node (ref "C38") (pin "2") (pinfunction "2_2") (pintype "passive"))
      (node (ref "C39") (pin "2") (pinfunction "2_2") (pintype "passive"))
      (node (ref "C4") (pin "2") (pinfunction "2_2") (pintype "passive"))
      (node (ref "C40") (pin "2") (pinfunction "2_2") (pintype "passive"))
      (node (ref "C41") (pin "-") (pinfunction "-_-") (pintype "passive"))
      (node (ref "C42") (pin "-") (pinfunction "-_-") (pintype "passive"))
      (node (ref "C5") (pin "2") (pinfunction "2_2") (pintype "passive"))
      (node (ref "C6") (pin "2") (pinfunction "2_2") (pintype "passive"))
      (node (ref "C7") (pin "2") (pinfunction "2_2") (pintype "passive"))
      (node (ref "C8") (pin "2") (pinfunction "2_2") (pintype "passive"))
      (node (ref "C9") (pin "2") (pinfunction "2_2") (pintype "passive"))
      (node (ref "Q1") (pin "1") (pinfunction "E_1") (pintype "passive"))
      (node (ref "Q2") (pin "1") (pinfunction "E_1") (pintype "passive"))
      (node (ref "Q3") (pin "1") (pinfunction "E_1") (pintype "passive"))
      (node (ref "Q4") (pin "1") (pinfunction "E_1") (pintype "passive"))
      (node (ref "Q5") (pin "1") (pinfunction "E_1") (pintype "passive"))
      (node (ref "Q6") (pin "1") (pinfunction "E_1") (pintype "passive"))
      (node (ref "Q7") (pin "1") (pinfunction "E_1") (pintype "passive"))
      (node (ref "Q8") (pin "1") (pinfunction "E_1") (pintype "passive"))
      (node (ref "R12") (pin "1") (pinfunction "1_1") (pintype "passive"))
      (node (ref "R15") (pin "1") (pinfunction "1_1") (pintype "passive"))
      (node (ref "R18") (pin "1") (pinfunction "1_1") (pintype "passive"))
      (node (ref "R21") (pin "1") (pinfunction "1_1") (pintype "passive"))
      (node (ref "R24") (pin "1") (pinfunction "1_1") (pintype "passive"))
      (node (ref "R3") (pin "1") (pinfunction "1_1") (pintype "passive"))
      (node (ref "R41") (pin "1") (pinfunction "1_1") (pintype "passive"))
      (node (ref "R42") (pin "1") (pinfunction "1_1") (pintype "passive"))
      (node (ref "R43") (pin "1") (pinfunction "1_1") (pintype "passive"))
      (node (ref "R44") (pin "1") (pinfunction "1_1") (pintype "passive"))
      (node (ref "R45") (pin "1") (pinfunction "1_1") (pintype "passive"))
      (node (ref "R46") (pin "1") (pinfunction "1_1") (pintype "passive"))
      (node (ref "R47") (pin "1") (pinfunction "1_1") (pintype "passive"))
      (node (ref "R48") (pin "1") (pinfunction "1_1") (pintype "passive"))
      (node (ref "R49") (pin "1") (pinfunction "1_1") (pintype "passive"))
      (node (ref "R50") (pin "1") (pinfunction "1_1") (pintype "passive"))
      (node (ref "R51") (pin "1") (pinfunction "1_1") (pintype "passive"))
      (node (ref "R52") (pin "1") (pinfunction "1_1") (pintype "passive"))
      (node (ref "R53") (pin "1") (pinfunction "1_1") (pintype "passive"))
      (node (ref "R54") (pin "1") (pinfunction "1_1") (pintype "passive"))
      (node (ref "R55") (pin "1") (pinfunction "1_1") (pintype "passive"))
      (node (ref "R56") (pin "1") (pinfunction "1_1") (pintype "passive"))
      (node (ref "R6") (pin "1") (pinfunction "1_1") (pintype "passive"))
      (node (ref "R9") (pin "1") (pinfunction "1_1") (pintype "passive"))
      (node (ref "U$3") (pin "AC2") (pinfunction "1_AC2") (pintype "bidirectional"))
      (node (ref "U$3") (pin "AT1") (pinfunction "1_AT1") (pintype "bidirectional"))
      (node (ref "U$3") (pin "BC2") (pinfunction "1_BC2") (pintype "bidirectional"))
      (node (ref "U$3") (pin "BT1") (pinfunction "1_BT1") (pintype "bidirectional"))
    )
    (net (code "10") (name "Net-(E1A-I1)") (class "Default")
      (node (ref "E1") (pin "3") (pinfunction "I1_3") (pintype "input"))
      (node (ref "E1") (pin "4") (pinfunction "O_4") (pintype "output"))
      (node (ref "E3") (pin "9") (pinfunction "R_9") (pintype "input"))
    )
    (net (code "11") (name "Net-(E1A-O)") (class "Default")
      (node (ref "E1") (pin "1") (pinfunction "O_1") (pintype "output"))
      (node (ref "E3") (pin "13") (pinfunction "S_13") (pintype "input"))
    )
    (net (code "12") (name "Net-(E1B-I1)") (class "Default")
      (node (ref "E1") (pin "6") (pinfunction "I1_6") (pintype "input"))
      (node (ref "U$3") (pin "AF2") (pinfunction "1_AF2") (pintype "bidirectional"))
    )
    (net (code "13") (name "Net-(E1C-I0)") (class "Default")
      (node (ref "E1") (pin "8") (pinfunction "I0_8") (pintype "input"))
      (node (ref "U$3") (pin "AE2") (pinfunction "1_AE2") (pintype "bidirectional"))
    )
    (net (code "14") (name "Net-(E1C-O)") (class "Default")
      (node (ref "E1") (pin "10") (pinfunction "O_10") (pintype "output"))
      (node (ref "E1") (pin "11") (pinfunction "I0_11") (pintype "input"))
      (node (ref "E4") (pin "9") (pinfunction "R_9") (pintype "input"))
    )
    (net (code "15") (name "Net-(E1D-O)") (class "Default")
      (node (ref "E1") (pin "13") (pinfunction "O_13") (pintype "output"))
      (node (ref "E4") (pin "13") (pinfunction "S_13") (pintype "input"))
    )
    (net (code "16") (name "Net-(E2A-I1)") (class "Default")
      (node (ref "E2") (pin "3") (pinfunction "I1_3") (pintype "input"))
      (node (ref "E2") (pin "4") (pinfunction "O_4") (pintype "output"))
      (node (ref "E6") (pin "9") (pinfunction "R_9") (pintype "input"))
    )
    (net (code "17") (name "Net-(E2A-O)") (class "Default")
      (node (ref "E2") (pin "1") (pinfunction "O_1") (pintype "output"))
      (node (ref "E6") (pin "13") (pinfunction "S_13") (pintype "input"))
    )
    (net (code "18") (name "Net-(E2B-I1)") (class "Default")
      (node (ref "E2") (pin "6") (pinfunction "I1_6") (pintype "input"))
      (node (ref "U$3") (pin "AA1") (pinfunction "1_AA1") (pintype "bidirectional"))
    )
    (net (code "19") (name "Net-(E2C-I1)") (class "Default")
      (node (ref "E2") (pin "9") (pinfunction "I1_9") (pintype "input"))
      (node (ref "U$3") (pin "AD2") (pinfunction "1_AD2") (pintype "bidirectional"))
    )
    (net (code "20") (name "Net-(E2C-O)") (class "Default")
      (node (ref "E2") (pin "10") (pinfunction "O_10") (pintype "output"))
      (node (ref "E2") (pin "11") (pinfunction "I0_11") (pintype "input"))
      (node (ref "E5") (pin "9") (pinfunction "R_9") (pintype "input"))
    )
    (net (code "21") (name "Net-(E2D-O)") (class "Default")
      (node (ref "E2") (pin "13") (pinfunction "O_13") (pintype "output"))
      (node (ref "E5") (pin "13") (pinfunction "S_13") (pintype "input"))
    )
    (net (code "22") (name "Net-(E3A-1)") (class "Default")
      (node (ref "E3") (pin "11") (pinfunction "1_11") (pintype "output"))
      (node (ref "R25") (pin "1") (pinfunction "1_1") (pintype "passive"))
      (node (ref "R41") (pin "2") (pinfunction "2_2") (pintype "passive"))
      (node (ref "U$3") (pin "AE1") (pinfunction "1_AE1") (pintype "bidirectional"))
    )
    (net (code "23") (name "Net-(E4A-1)") (class "Default")
      (node (ref "E4") (pin "11") (pinfunction "1_11") (pintype "output"))
      (node (ref "R29") (pin "1") (pinfunction "1_1") (pintype "passive"))
      (node (ref "R45") (pin "2") (pinfunction "2_2") (pintype "passive"))
      (node (ref "U$3") (pin "AF1") (pinfunction "1_AF1") (pintype "bidirectional"))
    )
    (net (code "24") (name "Net-(E5A-1)") (class "Default")
      (node (ref "E5") (pin "11") (pinfunction "1_11") (pintype "output"))
      (node (ref "R30") (pin "1") (pinfunction "1_1") (pintype "passive"))
      (node (ref "R46") (pin "2") (pinfunction "2_2") (pintype "passive"))
      (node (ref "U$3") (pin "AD1") (pinfunction "1_AD1") (pintype "bidirectional"))
    )
    (net (code "25") (name "Net-(E6A-1)") (class "Default")
      (node (ref "E6") (pin "11") (pinfunction "1_11") (pintype "output"))
      (node (ref "R26") (pin "1") (pinfunction "1_1") (pintype "passive"))
      (node (ref "R42") (pin "2") (pinfunction "2_2") (pintype "passive"))
      (node (ref "U$3") (pin "AC1") (pinfunction "1_AC1") (pintype "bidirectional"))
    )
    (net (code "26") (name "Net-(E7A-I4)") (class "Default")
      (node (ref "E7") (pin "1") (pinfunction "I4_1") (pintype "input"))
      (node (ref "U$3") (pin "AT2") (pinfunction "1_AT2") (pintype "bidirectional"))
    )
    (net (code "27") (name "Net-(E7A-I6)") (class "Default")
      (node (ref "E7") (pin "3") (pinfunction "I6_3") (pintype "input"))
      (node (ref "U$3") (pin "AS2") (pinfunction "1_AS2") (pintype "bidirectional"))
    )
    (net (code "28") (name "Net-(E7A-I8)") (class "Default")
      (node (ref "E7") (pin "9") (pinfunction "I8_9") (pintype "input"))
      (node (ref "U$3") (pin "AR1") (pinfunction "1_AR1") (pintype "bidirectional"))
    )
    (net (code "29") (name "Net-(E7A-I11)") (class "Default")
      (node (ref "E7") (pin "5") (pinfunction "I11_5") (pintype "input"))
      (node (ref "U$3") (pin "AR2") (pinfunction "1_AR2") (pintype "bidirectional"))
    )
    (net (code "30") (name "Net-(E8B-I1)") (class "Default")
      (node (ref "E8") (pin "6") (pinfunction "I1_6") (pintype "input"))
      (node (ref "U$3") (pin "AK2") (pinfunction "1_AK2") (pintype "bidirectional"))
    )
    (net (code "31") (name "Net-(E8C-I0)") (class "Default")
      (node (ref "E8") (pin "8") (pinfunction "I0_8") (pintype "input"))
      (node (ref "U$3") (pin "AJ2") (pinfunction "1_AJ2") (pintype "bidirectional"))
    )
    (net (code "32") (name "Net-(E9B-I1)") (class "Default")
      (node (ref "E9") (pin "6") (pinfunction "I1_6") (pintype "input"))
      (node (ref "U$3") (pin "AH1") (pinfunction "1_AH1") (pintype "bidirectional"))
    )
    (net (code "33") (name "Net-(E9C-I1)") (class "Default")
      (node (ref "E9") (pin "9") (pinfunction "I1_9") (pintype "input"))
      (node (ref "U$3") (pin "AH2") (pinfunction "1_AH2") (pintype "bidirectional"))
    )
    (net (code "34") (name "Net-(E10A-I0)") (class "Default")
      (node (ref "E10") (pin "2") (pinfunction "I0_2") (pintype "input"))
      (node (ref "E10") (pin "8") (pinfunction "I0_8") (pintype "input"))
      (node (ref "E16") (pin "8") (pinfunction "O_8") (pintype "output"))
    )
    (net (code "35") (name "Net-(E10A-I1)") (class "Default")
      (node (ref "E10") (pin "3") (pinfunction "I1_3") (pintype "input"))
      (node (ref "E10") (pin "5") (pinfunction "I0_5") (pintype "input"))
      (node (ref "E16") (pin "11") (pinfunction "O_11") (pintype "output"))
    )
    (net (code "36") (name "Net-(E10A-O)") (class "Default")
      (node (ref "E10") (pin "1") (pinfunction "O_1") (pintype "open_collector"))
      (node (ref "Q1") (pin "2") (pinfunction "B_2") (pintype "passive"))
      (node (ref "R1") (pin "1") (pinfunction "1_1") (pintype "passive"))
    )
    (net (code "37") (name "Net-(E10B-I1)") (class "Default")
      (node (ref "E10") (pin "12") (pinfunction "I1_12") (pintype "input"))
      (node (ref "E10") (pin "6") (pinfunction "I1_6") (pintype "input"))
      (node (ref "E11") (pin "8") (pinfunction "O_8") (pintype "output"))
      (node (ref "E16") (pin "10") (pinfunction "I1_10") (pintype "input"))
      (node (ref "E16") (pin "9") (pinfunction "I0_9") (pintype "input"))
    )
    (net (code "38") (name "Net-(E10B-O)") (class "Default")
      (node (ref "E10") (pin "4") (pinfunction "O_4") (pintype "open_collector"))
      (node (ref "Q2") (pin "2") (pinfunction "B_2") (pintype "passive"))
      (node (ref "R4") (pin "1") (pinfunction "1_1") (pintype "passive"))
    )
    (net (code "39") (name "Net-(E10C-I1)") (class "Default")
      (node (ref "E10") (pin "11") (pinfunction "I0_11") (pintype "input"))
      (node (ref "E10") (pin "9") (pinfunction "I1_9") (pintype "input"))
      (node (ref "E16") (pin "12") (pinfunction "I0_12") (pintype "input"))
      (node (ref "E16") (pin "13") (pinfunction "I1_13") (pintype "input"))
      (node (ref "E7") (pin "8") (pinfunction "O_8") (pintype "output"))
    )
    (net (code "40") (name "Net-(E10C-O)") (class "Default")
      (node (ref "E10") (pin "10") (pinfunction "O_10") (pintype "open_collector"))
      (node (ref "Q3") (pin "2") (pinfunction "B_2") (pintype "passive"))
      (node (ref "R7") (pin "1") (pinfunction "1_1") (pintype "passive"))
    )
    (net (code "41") (name "Net-(E10D-O)") (class "Default")
      (node (ref "E10") (pin "13") (pinfunction "O_13") (pintype "open_collector"))
      (node (ref "Q4") (pin "2") (pinfunction "B_2") (pintype "passive"))
      (node (ref "R10") (pin "1") (pinfunction "1_1") (pintype "passive"))
    )
    (net (code "42") (name "Net-(E11A-I1)") (class "Default")
      (node (ref "E11") (pin "4") (pinfunction "I1_4") (pintype "input"))
      (node (ref "E18") (pin "4") (pinfunction "I1_4") (pintype "input"))
      (node (ref "E22") (pin "4") (pinfunction "I1_4") (pintype "input"))
      (node (ref "E7") (pin "4") (pinfunction "I1_4") (pintype "input"))
      (node (ref "U$3") (pin "AP2") (pinfunction "1_AP2") (pintype "bidirectional"))
    )
    (net (code "43") (name "Net-(E11A-I3)") (class "Default")
      (node (ref "E11") (pin "13") (pinfunction "I3_13") (pintype "input"))
      (node (ref "E18") (pin "13") (pinfunction "I3_13") (pintype "input"))
      (node (ref "E22") (pin "13") (pinfunction "I3_13") (pintype "input"))
      (node (ref "E7") (pin "13") (pinfunction "I3_13") (pintype "input"))
      (node (ref "U$3") (pin "BE1") (pinfunction "1_BE1") (pintype "bidirectional"))
    )
    (net (code "44") (name "Net-(E11A-I4)") (class "Default")
      (node (ref "E11") (pin "1") (pinfunction "I4_1") (pintype "input"))
      (node (ref "U$3") (pin "AV2") (pinfunction "1_AV2") (pintype "bidirectional"))
    )
    (net (code "45") (name "Net-(E11A-I5)") (class "Default")
      (node (ref "E11") (pin "2") (pinfunction "I5_2") (pintype "input"))
      (node (ref "E18") (pin "2") (pinfunction "I5_2") (pintype "input"))
      (node (ref "E22") (pin "2") (pinfunction "I5_2") (pintype "input"))
      (node (ref "E7") (pin "2") (pinfunction "I5_2") (pintype "input"))
      (node (ref "U$3") (pin "BJ1") (pinfunction "1_BJ1") (pintype "bidirectional"))
    )
    (net (code "46") (name "Net-(E11A-I6)") (class "Default")
      (node (ref "E11") (pin "3") (pinfunction "I6_3") (pintype "input"))
      (node (ref "U$3") (pin "AV1") (pinfunction "1_AV1") (pintype "bidirectional"))
    )
    (net (code "47") (name "Net-(E11A-I7)") (class "Default")
      (node (ref "E11") (pin "10") (pinfunction "I7_10") (pintype "input"))
      (node (ref "E18") (pin "10") (pinfunction "I7_10") (pintype "input"))
      (node (ref "E22") (pin "10") (pinfunction "I7_10") (pintype "input"))
      (node (ref "E7") (pin "10") (pinfunction "I7_10") (pintype "input"))
      (node (ref "U$3") (pin "AS1") (pinfunction "1_AS1") (pintype "bidirectional"))
    )
    (net (code "48") (name "Net-(E11A-I8)") (class "Default")
      (node (ref "E11") (pin "9") (pinfunction "I8_9") (pintype "input"))
      (node (ref "U$3") (pin "AU2") (pinfunction "1_AU2") (pintype "bidirectional"))
    )
    (net (code "49") (name "Net-(E11A-I11)") (class "Default")
      (node (ref "E11") (pin "5") (pinfunction "I11_5") (pintype "input"))
      (node (ref "U$3") (pin "AU1") (pinfunction "1_AU1") (pintype "bidirectional"))
    )
    (net (code "50") (name "Net-(E12A-1)") (class "Default")
      (node (ref "E12") (pin "11") (pinfunction "1_11") (pintype "output"))
      (node (ref "R27") (pin "1") (pinfunction "1_1") (pintype "passive"))
      (node (ref "R43") (pin "2") (pinfunction "2_2") (pintype "passive"))
      (node (ref "U$3") (pin "AL1") (pinfunction "1_AL1") (pintype "bidirectional"))
    )
    (net (code "51") (name "Net-(E12A-R)") (class "Default")
      (node (ref "E12") (pin "9") (pinfunction "R_9") (pintype "input"))
      (node (ref "E8") (pin "3") (pinfunction "I1_3") (pintype "input"))
      (node (ref "E8") (pin "4") (pinfunction "O_4") (pintype "output"))
    )
    (net (code "52") (name "Net-(E12A-S)") (class "Default")
      (node (ref "E12") (pin "13") (pinfunction "S_13") (pintype "input"))
      (node (ref "E8") (pin "1") (pinfunction "O_1") (pintype "output"))
    )
    (net (code "53") (name "Net-(E13A-1)") (class "Default")
      (node (ref "E13") (pin "11") (pinfunction "1_11") (pintype "output"))
      (node (ref "R31") (pin "1") (pinfunction "1_1") (pintype "passive"))
      (node (ref "R47") (pin "2") (pinfunction "2_2") (pintype "passive"))
      (node (ref "U$3") (pin "AM1") (pinfunction "1_AM1") (pintype "bidirectional"))
    )
    (net (code "54") (name "Net-(E13A-R)") (class "Default")
      (node (ref "E13") (pin "9") (pinfunction "R_9") (pintype "input"))
      (node (ref "E8") (pin "10") (pinfunction "O_10") (pintype "output"))
      (node (ref "E8") (pin "11") (pinfunction "I0_11") (pintype "input"))
    )
    (net (code "55") (name "Net-(E13A-S)") (class "Default")
      (node (ref "E13") (pin "13") (pinfunction "S_13") (pintype "input"))
      (node (ref "E8") (pin "13") (pinfunction "O_13") (pintype "output"))
    )
    (net (code "56") (name "Net-(E14A-1)") (class "Default")
      (node (ref "E14") (pin "11") (pinfunction "1_11") (pintype "output"))
      (node (ref "R32") (pin "1") (pinfunction "1_1") (pintype "passive"))
      (node (ref "R48") (pin "2") (pinfunction "2_2") (pintype "passive"))
      (node (ref "U$3") (pin "AK1") (pinfunction "1_AK1") (pintype "bidirectional"))
    )
    (net (code "57") (name "Net-(E14A-R)") (class "Default")
      (node (ref "E14") (pin "9") (pinfunction "R_9") (pintype "input"))
      (node (ref "E9") (pin "10") (pinfunction "O_10") (pintype "output"))
      (node (ref "E9") (pin "11") (pinfunction "I0_11") (pintype "input"))
    )
    (net (code "58") (name "Net-(E14A-S)") (class "Default")
      (node (ref "E14") (pin "13") (pinfunction "S_13") (pintype "input"))
      (node (ref "E9") (pin "13") (pinfunction "O_13") (pintype "output"))
    )
    (net (code "59") (name "Net-(E15A-1)") (class "Default")
      (node (ref "E15") (pin "11") (pinfunction "1_11") (pintype "output"))
      (node (ref "R28") (pin "1") (pinfunction "1_1") (pintype "passive"))
      (node (ref "R44") (pin "2") (pinfunction "2_2") (pintype "passive"))
      (node (ref "U$3") (pin "AJ1") (pinfunction "1_AJ1") (pintype "bidirectional"))
    )
    (net (code "60") (name "Net-(E15A-R)") (class "Default")
      (node (ref "E15") (pin "9") (pinfunction "R_9") (pintype "input"))
      (node (ref "E9") (pin "3") (pinfunction "I1_3") (pintype "input"))
      (node (ref "E9") (pin "4") (pinfunction "O_4") (pintype "output"))
    )
    (net (code "61") (name "Net-(E15A-S)") (class "Default")
      (node (ref "E15") (pin "13") (pinfunction "S_13") (pintype "input"))
      (node (ref "E9") (pin "1") (pinfunction "O_1") (pintype "output"))
    )
    (net (code "62") (name "Net-(E16A-I0)") (class "Default")
      (node (ref "E16") (pin "1") (pinfunction "I0_1") (pintype "input"))
      (node (ref "E16") (pin "2") (pinfunction "I1_2") (pintype "input"))
      (node (ref "E21") (pin "12") (pinfunction "I1_12") (pintype "input"))
      (node (ref "E21") (pin "6") (pinfunction "I1_6") (pintype "input"))
      (node (ref "E22") (pin "8") (pinfunction "O_8") (pintype "output"))
    )
    (net (code "63") (name "Net-(E16A-O)") (class "Default")
      (node (ref "E16") (pin "3") (pinfunction "O_3") (pintype "output"))
      (node (ref "E21") (pin "2") (pinfunction "I0_2") (pintype "input"))
      (node (ref "E21") (pin "8") (pinfunction "I0_8") (pintype "input"))
    )
    (net (code "64") (name "Net-(E16B-I0)") (class "Default")
      (node (ref "E16") (pin "4") (pinfunction "I0_4") (pintype "input"))
      (node (ref "E16") (pin "5") (pinfunction "I1_5") (pintype "input"))
      (node (ref "E18") (pin "8") (pinfunction "O_8") (pintype "output"))
      (node (ref "E21") (pin "11") (pinfunction "I0_11") (pintype "input"))
      (node (ref "E21") (pin "9") (pinfunction "I1_9") (pintype "input"))
    )
    (net (code "65") (name "Net-(E16B-O)") (class "Default")
      (node (ref "E16") (pin "6") (pinfunction "O_6") (pintype "output"))
      (node (ref "E21") (pin "3") (pinfunction "I1_3") (pintype "input"))
      (node (ref "E21") (pin "5") (pinfunction "I0_5") (pintype "input"))
    )
    (net (code "66") (name "Net-(E17C-I0)") (class "Default")
      (node (ref "E17") (pin "1") (pinfunction "I0_1") (pintype "input"))
      (node (ref "E17") (pin "2") (pinfunction "I1_2") (pintype "input"))
      (node (ref "E17") (pin "4") (pinfunction "I2_4") (pintype "input"))
      (node (ref "E17") (pin "5") (pinfunction "I3_5") (pintype "input"))
      (node (ref "U$3") (pin "BK1") (pinfunction "1_BK1") (pintype "bidirectional"))
    )
    (net (code "67") (name "Net-(E17C-O)") (class "Default")
      (node (ref "E17") (pin "6") (pinfunction "O_6") (pintype "output"))
      (node (ref "E19") (pin "12") (pinfunction "I1_12") (pintype "input"))
      (node (ref "E19") (pin "2") (pinfunction "I0_2") (pintype "input"))
      (node (ref "E19") (pin "5") (pinfunction "I0_5") (pintype "input"))
      (node (ref "E19") (pin "9") (pinfunction "I1_9") (pintype "input"))
      (node (ref "E20") (pin "12") (pinfunction "I1_12") (pintype "input"))
      (node (ref "E20") (pin "2") (pinfunction "I0_2") (pintype "input"))
      (node (ref "E20") (pin "5") (pinfunction "I0_5") (pintype "input"))
      (node (ref "E20") (pin "8") (pinfunction "I0_8") (pintype "input"))
      (node (ref "E27") (pin "12") (pinfunction "I1_12") (pintype "input"))
      (node (ref "E27") (pin "2") (pinfunction "I0_2") (pintype "input"))
      (node (ref "E27") (pin "5") (pinfunction "I0_5") (pintype "input"))
      (node (ref "E27") (pin "9") (pinfunction "I1_9") (pintype "input"))
      (node (ref "E28") (pin "12") (pinfunction "I1_12") (pintype "input"))
      (node (ref "E28") (pin "2") (pinfunction "I0_2") (pintype "input"))
      (node (ref "E28") (pin "5") (pinfunction "I0_5") (pintype "input"))
      (node (ref "E28") (pin "8") (pinfunction "I0_8") (pintype "input"))
    )
    (net (code "68") (name "Net-(E17D-I0)") (class "Default")
      (node (ref "E17") (pin "10") (pinfunction "I1_10") (pintype "input"))
      (node (ref "E17") (pin "12") (pinfunction "I2_12") (pintype "input"))
      (node (ref "E17") (pin "13") (pinfunction "I3_13") (pintype "input"))
      (node (ref "E17") (pin "9") (pinfunction "I0_9") (pintype "input"))
      (node (ref "U$3") (pin "AM2") (pinfunction "1_AM2") (pintype "bidirectional"))
    )
    (net (code "69") (name "Net-(E17D-O)") (class "Default")
      (node (ref "E1") (pin "12") (pinfunction "I1_12") (pintype "input"))
      (node (ref "E1") (pin "2") (pinfunction "I0_2") (pintype "input"))
      (node (ref "E1") (pin "5") (pinfunction "I0_5") (pintype "input"))
      (node (ref "E1") (pin "9") (pinfunction "I1_9") (pintype "input"))
      (node (ref "E17") (pin "8") (pinfunction "O_8") (pintype "output"))
      (node (ref "E2") (pin "12") (pinfunction "I1_12") (pintype "input"))
      (node (ref "E2") (pin "2") (pinfunction "I0_2") (pintype "input"))
      (node (ref "E2") (pin "5") (pinfunction "I0_5") (pintype "input"))
      (node (ref "E2") (pin "8") (pinfunction "I0_8") (pintype "input"))
      (node (ref "E8") (pin "12") (pinfunction "I1_12") (pintype "input"))
      (node (ref "E8") (pin "2") (pinfunction "I0_2") (pintype "input"))
      (node (ref "E8") (pin "5") (pinfunction "I0_5") (pintype "input"))
      (node (ref "E8") (pin "9") (pinfunction "I1_9") (pintype "input"))
      (node (ref "E9") (pin "12") (pinfunction "I1_12") (pintype "input"))
      (node (ref "E9") (pin "2") (pinfunction "I0_2") (pintype "input"))
      (node (ref "E9") (pin "5") (pinfunction "I0_5") (pintype "input"))
      (node (ref "E9") (pin "8") (pinfunction "I0_8") (pintype "input"))
    )
    (net (code "70") (name "Net-(E18A-I4)") (class "Default")
      (node (ref "E18") (pin "1") (pinfunction "I4_1") (pintype "input"))
      (node (ref "U$3") (pin "BD1") (pinfunction "1_BD1") (pintype "bidirectional"))
    )
    (net (code "71") (name "Net-(E18A-I6)") (class "Default")
      (node (ref "E18") (pin "3") (pinfunction "I6_3") (pintype "input"))
      (node (ref "U$3") (pin "BD2") (pinfunction "1_BD2") (pintype "bidirectional"))
    )
    (net (code "72") (name "Net-(E18A-I8)") (class "Default")
      (node (ref "E18") (pin "9") (pinfunction "I8_9") (pintype "input"))
      (node (ref "U$3") (pin "BA1") (pinfunction "1_BA1") (pintype "bidirectional"))
    )
    (net (code "73") (name "Net-(E18A-I11)") (class "Default")
      (node (ref "E18") (pin "5") (pinfunction "I11_5") (pintype "input"))
      (node (ref "U$3") (pin "BC1") (pinfunction "1_BC1") (pintype "bidirectional"))
    )
    (net (code "74") (name "Net-(E19A-I1)") (class "Default")
      (node (ref "E19") (pin "3") (pinfunction "I1_3") (pintype "input"))
      (node (ref "E19") (pin "4") (pinfunction "O_4") (pintype "output"))
      (node (ref "E23") (pin "9") (pinfunction "R_9") (pintype "input"))
    )
    (net (code "75") (name "Net-(E19A-O)") (class "Default")
      (node (ref "E19") (pin "1") (pinfunction "O_1") (pintype "output"))
      (node (ref "E23") (pin "13") (pinfunction "S_13") (pintype "input"))
    )
    (net (code "76") (name "Net-(E19B-I1)") (class "Default")
      (node (ref "E19") (pin "6") (pinfunction "I1_6") (pintype "input"))
      (node (ref "U$3") (pin "BR2") (pinfunction "1_BR2") (pintype "bidirectional"))
    )
    (net (code "77") (name "Net-(E19C-I0)") (class "Default")
      (node (ref "E19") (pin "8") (pinfunction "I0_8") (pintype "input"))
      (node (ref "U$3") (pin "BP2") (pinfunction "1_BP2") (pintype "bidirectional"))
    )
    (net (code "78") (name "Net-(E19C-O)") (class "Default")
      (node (ref "E19") (pin "10") (pinfunction "O_10") (pintype "output"))
      (node (ref "E19") (pin "11") (pinfunction "I0_11") (pintype "input"))
      (node (ref "E24") (pin "9") (pinfunction "R_9") (pintype "input"))
    )
    (net (code "79") (name "Net-(E19D-O)") (class "Default")
      (node (ref "E19") (pin "13") (pinfunction "O_13") (pintype "output"))
      (node (ref "E24") (pin "13") (pinfunction "S_13") (pintype "input"))
    )
    (net (code "80") (name "Net-(E20A-I1)") (class "Default")
      (node (ref "E20") (pin "3") (pinfunction "I1_3") (pintype "input"))
      (node (ref "E20") (pin "4") (pinfunction "O_4") (pintype "output"))
      (node (ref "E26") (pin "9") (pinfunction "R_9") (pintype "input"))
    )
    (net (code "81") (name "Net-(E20A-O)") (class "Default")
      (node (ref "E20") (pin "1") (pinfunction "O_1") (pintype "output"))
      (node (ref "E26") (pin "13") (pinfunction "S_13") (pintype "input"))
    )
    (net (code "82") (name "Net-(E20B-I1)") (class "Default")
      (node (ref "E20") (pin "6") (pinfunction "I1_6") (pintype "input"))
      (node (ref "U$3") (pin "BL1") (pinfunction "1_BL1") (pintype "bidirectional"))
    )
    (net (code "83") (name "Net-(E20C-I1)") (class "Default")
      (node (ref "E20") (pin "9") (pinfunction "I1_9") (pintype "input"))
      (node (ref "U$3") (pin "BN2") (pinfunction "1_BN2") (pintype "bidirectional"))
    )
    (net (code "84") (name "Net-(E20C-O)") (class "Default")
      (node (ref "E20") (pin "10") (pinfunction "O_10") (pintype "output"))
      (node (ref "E20") (pin "11") (pinfunction "I0_11") (pintype "input"))
      (node (ref "E25") (pin "9") (pinfunction "R_9") (pintype "input"))
    )
    (net (code "85") (name "Net-(E20D-O)") (class "Default")
      (node (ref "E20") (pin "13") (pinfunction "O_13") (pintype "output"))
      (node (ref "E25") (pin "13") (pinfunction "S_13") (pintype "input"))
    )
    (net (code "86") (name "Net-(E21A-O)") (class "Default")
      (node (ref "E21") (pin "1") (pinfunction "O_1") (pintype "open_collector"))
      (node (ref "Q5") (pin "2") (pinfunction "B_2") (pintype "passive"))
      (node (ref "R13") (pin "1") (pinfunction "1_1") (pintype "passive"))
    )
    (net (code "87") (name "Net-(E21B-O)") (class "Default")
      (node (ref "E21") (pin "4") (pinfunction "O_4") (pintype "open_collector"))
      (node (ref "Q6") (pin "2") (pinfunction "B_2") (pintype "passive"))
      (node (ref "R16") (pin "1") (pinfunction "1_1") (pintype "passive"))
    )
    (net (code "88") (name "Net-(E21C-O)") (class "Default")
      (node (ref "E21") (pin "10") (pinfunction "O_10") (pintype "open_collector"))
      (node (ref "Q7") (pin "2") (pinfunction "B_2") (pintype "passive"))
      (node (ref "R19") (pin "1") (pinfunction "1_1") (pintype "passive"))
    )
    (net (code "89") (name "Net-(E21D-O)") (class "Default")
      (node (ref "E21") (pin "13") (pinfunction "O_13") (pintype "open_collector"))
      (node (ref "Q8") (pin "2") (pinfunction "B_2") (pintype "passive"))
      (node (ref "R22") (pin "1") (pinfunction "1_1") (pintype "passive"))
    )
    (net (code "90") (name "Net-(E22A-I4)") (class "Default")
      (node (ref "E22") (pin "1") (pinfunction "I4_1") (pintype "input"))
      (node (ref "U$3") (pin "BF2") (pinfunction "1_BF2") (pintype "bidirectional"))
    )
    (net (code "91") (name "Net-(E22A-I6)") (class "Default")
      (node (ref "E22") (pin "3") (pinfunction "I6_3") (pintype "input"))
      (node (ref "U$3") (pin "BH1") (pinfunction "1_BH1") (pintype "bidirectional"))
    )
    (net (code "92") (name "Net-(E22A-I8)") (class "Default")
      (node (ref "E22") (pin "9") (pinfunction "I8_9") (pintype "input"))
      (node (ref "U$3") (pin "BF1") (pinfunction "1_BF1") (pintype "bidirectional"))
    )
    (net (code "93") (name "Net-(E22A-I11)") (class "Default")
      (node (ref "E22") (pin "5") (pinfunction "I11_5") (pintype "input"))
      (node (ref "U$3") (pin "BE2") (pinfunction "1_BE2") (pintype "bidirectional"))
    )
    (net (code "94") (name "Net-(E23A-1)") (class "Default")
      (node (ref "E23") (pin "11") (pinfunction "1_11") (pintype "output"))
      (node (ref "R33") (pin "1") (pinfunction "1_1") (pintype "passive"))
      (node (ref "R49") (pin "2") (pinfunction "2_2") (pintype "passive"))
      (node (ref "U$3") (pin "BM2") (pinfunction "1_BM2") (pintype "bidirectional"))
    )
    (net (code "95") (name "Net-(E24A-1)") (class "Default")
      (node (ref "E24") (pin "11") (pinfunction "1_11") (pintype "output"))
      (node (ref "R37") (pin "1") (pinfunction "1_1") (pintype "passive"))
      (node (ref "R53") (pin "2") (pinfunction "2_2") (pintype "passive"))
      (node (ref "U$3") (pin "BT2") (pinfunction "1_BT2") (pintype "bidirectional"))
    )
    (net (code "96") (name "Net-(E25A-1)") (class "Default")
      (node (ref "E25") (pin "11") (pinfunction "1_11") (pintype "output"))
      (node (ref "R38") (pin "1") (pinfunction "1_1") (pintype "passive"))
      (node (ref "R54") (pin "2") (pinfunction "2_2") (pintype "passive"))
      (node (ref "U$3") (pin "BN1") (pinfunction "1_BN1") (pintype "bidirectional"))
    )
    (net (code "97") (name "Net-(E26A-1)") (class "Default")
      (node (ref "E26") (pin "11") (pinfunction "1_11") (pintype "output"))
      (node (ref "R34") (pin "1") (pinfunction "1_1") (pintype "passive"))
      (node (ref "R50") (pin "2") (pinfunction "2_2") (pintype "passive"))
      (node (ref "U$3") (pin "BM1") (pinfunction "1_BM1") (pintype "bidirectional"))
    )
    (net (code "98") (name "Net-(E27A-I1)") (class "Default")
      (node (ref "E27") (pin "3") (pinfunction "I1_3") (pintype "input"))
      (node (ref "E27") (pin "4") (pinfunction "O_4") (pintype "output"))
      (node (ref "E29") (pin "9") (pinfunction "R_9") (pintype "input"))
    )
    (net (code "99") (name "Net-(E27A-O)") (class "Default")
      (node (ref "E27") (pin "1") (pinfunction "O_1") (pintype "output"))
      (node (ref "E29") (pin "13") (pinfunction "S_13") (pintype "input"))
    )
    (net (code "100") (name "Net-(E27B-I1)") (class "Default")
      (node (ref "E27") (pin "6") (pinfunction "I1_6") (pintype "input"))
      (node (ref "U$3") (pin "BV2") (pinfunction "1_BV2") (pintype "bidirectional"))
    )
    (net (code "101") (name "Net-(E27C-I0)") (class "Default")
      (node (ref "E27") (pin "8") (pinfunction "I0_8") (pintype "input"))
      (node (ref "U$3") (pin "BU2") (pinfunction "1_BU2") (pintype "bidirectional"))
    )
    (net (code "102") (name "Net-(E27C-O)") (class "Default")
      (node (ref "E27") (pin "10") (pinfunction "O_10") (pintype "output"))
      (node (ref "E27") (pin "11") (pinfunction "I0_11") (pintype "input"))
      (node (ref "E30") (pin "9") (pinfunction "R_9") (pintype "input"))
    )
    (net (code "103") (name "Net-(E27D-O)") (class "Default")
      (node (ref "E27") (pin "13") (pinfunction "O_13") (pintype "output"))
      (node (ref "E30") (pin "13") (pinfunction "S_13") (pintype "input"))
    )
    (net (code "104") (name "Net-(E28A-I1)") (class "Default")
      (node (ref "E28") (pin "3") (pinfunction "I1_3") (pintype "input"))
      (node (ref "E28") (pin "4") (pinfunction "O_4") (pintype "output"))
      (node (ref "E32") (pin "9") (pinfunction "R_9") (pintype "input"))
    )
    (net (code "105") (name "Net-(E28A-O)") (class "Default")
      (node (ref "E28") (pin "1") (pinfunction "O_1") (pintype "output"))
      (node (ref "E32") (pin "13") (pinfunction "S_13") (pintype "input"))
    )
    (net (code "106") (name "Net-(E28B-I1)") (class "Default")
      (node (ref "E28") (pin "6") (pinfunction "I1_6") (pintype "input"))
      (node (ref "U$3") (pin "BP1") (pinfunction "1_BP1") (pintype "bidirectional"))
    )
    (net (code "107") (name "Net-(E28C-I1)") (class "Default")
      (node (ref "E28") (pin "9") (pinfunction "I1_9") (pintype "input"))
      (node (ref "U$3") (pin "BS2") (pinfunction "1_BS2") (pintype "bidirectional"))
    )
    (net (code "108") (name "Net-(E28C-O)") (class "Default")
      (node (ref "E28") (pin "10") (pinfunction "O_10") (pintype "output"))
      (node (ref "E28") (pin "11") (pinfunction "I0_11") (pintype "input"))
      (node (ref "E31") (pin "9") (pinfunction "R_9") (pintype "input"))
    )
    (net (code "109") (name "Net-(E28D-O)") (class "Default")
      (node (ref "E28") (pin "13") (pinfunction "O_13") (pintype "output"))
      (node (ref "E31") (pin "13") (pinfunction "S_13") (pintype "input"))
    )
    (net (code "110") (name "Net-(E29A-1)") (class "Default")
      (node (ref "E29") (pin "11") (pinfunction "1_11") (pintype "output"))
      (node (ref "R35") (pin "1") (pinfunction "1_1") (pintype "passive"))
      (node (ref "R51") (pin "2") (pinfunction "2_2") (pintype "passive"))
      (node (ref "U$3") (pin "BU1") (pinfunction "1_BU1") (pintype "bidirectional"))
    )
    (net (code "111") (name "Net-(E30A-1)") (class "Default")
      (node (ref "E30") (pin "11") (pinfunction "1_11") (pintype "output"))
      (node (ref "R39") (pin "1") (pinfunction "1_1") (pintype "passive"))
      (node (ref "R55") (pin "2") (pinfunction "2_2") (pintype "passive"))
      (node (ref "U$3") (pin "BV1") (pinfunction "1_BV1") (pintype "bidirectional"))
    )
    (net (code "112") (name "Net-(E31A-1)") (class "Default")
      (node (ref "E31") (pin "11") (pinfunction "1_11") (pintype "output"))
      (node (ref "R40") (pin "1") (pinfunction "1_1") (pintype "passive"))
      (node (ref "R56") (pin "2") (pinfunction "2_2") (pintype "passive"))
      (node (ref "U$3") (pin "BS1") (pinfunction "1_BS1") (pintype "bidirectional"))
    )
    (net (code "113") (name "Net-(E32A-1)") (class "Default")
      (node (ref "E32") (pin "11") (pinfunction "1_11") (pintype "output"))
      (node (ref "R36") (pin "1") (pinfunction "1_1") (pintype "passive"))
      (node (ref "R52") (pin "2") (pinfunction "2_2") (pintype "passive"))
      (node (ref "U$3") (pin "BR1") (pinfunction "1_BR1") (pintype "bidirectional"))
    )
    (net (code "114") (name "VCC") (class "Default")
      (node (ref "C1") (pin "1") (pinfunction "1_1") (pintype "passive"))
      (node (ref "C10") (pin "1") (pinfunction "1_1") (pintype "passive"))
      (node (ref "C11") (pin "1") (pinfunction "1_1") (pintype "passive"))
      (node (ref "C12") (pin "1") (pinfunction "1_1") (pintype "passive"))
      (node (ref "C13") (pin "1") (pinfunction "1_1") (pintype "passive"))
      (node (ref "C14") (pin "1") (pinfunction "1_1") (pintype "passive"))
      (node (ref "C15") (pin "1") (pinfunction "1_1") (pintype "passive"))
      (node (ref "C16") (pin "1") (pinfunction "1_1") (pintype "passive"))
      (node (ref "C17") (pin "1") (pinfunction "1_1") (pintype "passive"))
      (node (ref "C18") (pin "1") (pinfunction "1_1") (pintype "passive"))
      (node (ref "C19") (pin "1") (pinfunction "1_1") (pintype "passive"))
      (node (ref "C2") (pin "1") (pinfunction "1_1") (pintype "passive"))
      (node (ref "C20") (pin "1") (pinfunction "1_1") (pintype "passive"))
      (node (ref "C21") (pin "1") (pinfunction "1_1") (pintype "passive"))
      (node (ref "C22") (pin "1") (pinfunction "1_1") (pintype "passive"))
      (node (ref "C23") (pin "1") (pinfunction "1_1") (pintype "passive"))
      (node (ref "C24") (pin "1") (pinfunction "1_1") (pintype "passive"))
      (node (ref "C25") (pin "1") (pinfunction "1_1") (pintype "passive"))
      (node (ref "C26") (pin "1") (pinfunction "1_1") (pintype "passive"))
      (node (ref "C27") (pin "1") (pinfunction "1_1") (pintype "passive"))
      (node (ref "C28") (pin "1") (pinfunction "1_1") (pintype "passive"))
      (node (ref "C29") (pin "1") (pinfunction "1_1") (pintype "passive"))
      (node (ref "C3") (pin "1") (pinfunction "1_1") (pintype "passive"))
      (node (ref "C30") (pin "1") (pinfunction "1_1") (pintype "passive"))
      (node (ref "C31") (pin "1") (pinfunction "1_1") (pintype "passive"))
      (node (ref "C32") (pin "1") (pinfunction "1_1") (pintype "passive"))
      (node (ref "C33") (pin "1") (pinfunction "1_1") (pintype "passive"))
      (node (ref "C34") (pin "1") (pinfunction "1_1") (pintype "passive"))
      (node (ref "C35") (pin "1") (pinfunction "1_1") (pintype "passive"))
      (node (ref "C36") (pin "1") (pinfunction "1_1") (pintype "passive"))
      (node (ref "C37") (pin "1") (pinfunction "1_1") (pintype "passive"))
      (node (ref "C38") (pin "1") (pinfunction "1_1") (pintype "passive"))
      (node (ref "C39") (pin "1") (pinfunction "1_1") (pintype "passive"))
      (node (ref "C4") (pin "1") (pinfunction "1_1") (pintype "passive"))
      (node (ref "C40") (pin "1") (pinfunction "1_1") (pintype "passive"))
      (node (ref "C41") (pin "+") (pinfunction "+_+") (pintype "passive"))
      (node (ref "C42") (pin "+") (pinfunction "+_+") (pintype "passive"))
      (node (ref "C5") (pin "1") (pinfunction "1_1") (pintype "passive"))
      (node (ref "C6") (pin "1") (pinfunction "1_1") (pintype "passive"))
      (node (ref "C7") (pin "1") (pinfunction "1_1") (pintype "passive"))
      (node (ref "C8") (pin "1") (pinfunction "1_1") (pintype "passive"))
      (node (ref "C9") (pin "1") (pinfunction "1_1") (pintype "passive"))
      (node (ref "R1") (pin "2") (pinfunction "2_2") (pintype "passive"))
      (node (ref "R10") (pin "2") (pinfunction "2_2") (pintype "passive"))
      (node (ref "R11") (pin "2") (pinfunction "2_2") (pintype "passive"))
      (node (ref "R13") (pin "2") (pinfunction "2_2") (pintype "passive"))
      (node (ref "R14") (pin "2") (pinfunction "2_2") (pintype "passive"))
      (node (ref "R16") (pin "2") (pinfunction "2_2") (pintype "passive"))
      (node (ref "R17") (pin "2") (pinfunction "2_2") (pintype "passive"))
      (node (ref "R19") (pin "2") (pinfunction "2_2") (pintype "passive"))
      (node (ref "R2") (pin "2") (pinfunction "2_2") (pintype "passive"))
      (node (ref "R20") (pin "2") (pinfunction "2_2") (pintype "passive"))
      (node (ref "R22") (pin "2") (pinfunction "2_2") (pintype "passive"))
      (node (ref "R23") (pin "2") (pinfunction "2_2") (pintype "passive"))
      (node (ref "R25") (pin "2") (pinfunction "2_2") (pintype "passive"))
      (node (ref "R26") (pin "2") (pinfunction "2_2") (pintype "passive"))
      (node (ref "R27") (pin "2") (pinfunction "2_2") (pintype "passive"))
      (node (ref "R28") (pin "2") (pinfunction "2_2") (pintype "passive"))
      (node (ref "R29") (pin "2") (pinfunction "2_2") (pintype "passive"))
      (node (ref "R30") (pin "2") (pinfunction "2_2") (pintype "passive"))
      (node (ref "R31") (pin "2") (pinfunction "2_2") (pintype "passive"))
      (node (ref "R32") (pin "2") (pinfunction "2_2") (pintype "passive"))
      (node (ref "R33") (pin "2") (pinfunction "2_2") (pintype "passive"))
      (node (ref "R34") (pin "2") (pinfunction "2_2") (pintype "passive"))
      (node (ref "R35") (pin "2") (pinfunction "2_2") (pintype "passive"))
      (node (ref "R36") (pin "2") (pinfunction "2_2") (pintype "passive"))
      (node (ref "R37") (pin "2") (pinfunction "2_2") (pintype "passive"))
      (node (ref "R38") (pin "2") (pinfunction "2_2") (pintype "passive"))
      (node (ref "R39") (pin "2") (pinfunction "2_2") (pintype "passive"))
      (node (ref "R4") (pin "2") (pinfunction "2_2") (pintype "passive"))
      (node (ref "R40") (pin "2") (pinfunction "2_2") (pintype "passive"))
      (node (ref "R5") (pin "2") (pinfunction "2_2") (pintype "passive"))
      (node (ref "R7") (pin "2") (pinfunction "2_2") (pintype "passive"))
      (node (ref "R8") (pin "2") (pinfunction "2_2") (pintype "passive"))
      (node (ref "U$3") (pin "AA2") (pinfunction "1_AA2") (pintype "bidirectional"))
      (node (ref "U$3") (pin "BA2") (pinfunction "1_BA2") (pintype "bidirectional"))
    )
    (net (code "115") (name "unconnected-(E3A-0-Pad12)") (class "Default")
      (node (ref "E3") (pin "12") (pinfunction "0_12") (pintype "output"))
    )
    (net (code "116") (name "unconnected-(E4A-0-Pad12)") (class "Default")
      (node (ref "E4") (pin "12") (pinfunction "0_12") (pintype "output"))
    )
    (net (code "117") (name "unconnected-(E5A-0-Pad12)") (class "Default")
      (node (ref "E5") (pin "12") (pinfunction "0_12") (pintype "output"))
    )
    (net (code "118") (name "unconnected-(E6A-0-Pad12)") (class "Default")
      (node (ref "E6") (pin "12") (pinfunction "0_12") (pintype "output"))
    )
    (net (code "119") (name "unconnected-(E7A-I2-Pad6)") (class "Default")
      (node (ref "E7") (pin "6") (pinfunction "I2_6") (pintype "input"))
    )
    (net (code "120") (name "unconnected-(E7A-I9-Pad12)") (class "Default")
      (node (ref "E7") (pin "12") (pinfunction "I9_12") (pintype "passive"))
    )
    (net (code "121") (name "unconnected-(E7A-I10-Pad11)") (class "Default")
      (node (ref "E7") (pin "11") (pinfunction "I10_11") (pintype "passive"))
    )
    (net (code "122") (name "unconnected-(E11A-I2-Pad6)") (class "Default")
      (node (ref "E11") (pin "6") (pinfunction "I2_6") (pintype "input"))
    )
    (net (code "123") (name "unconnected-(E11A-I9-Pad12)") (class "Default")
      (node (ref "E11") (pin "12") (pinfunction "I9_12") (pintype "passive"))
    )
    (net (code "124") (name "unconnected-(E11A-I10-Pad11)") (class "Default")
      (node (ref "E11") (pin "11") (pinfunction "I10_11") (pintype "passive"))
    )
    (net (code "125") (name "unconnected-(E12A-0-Pad12)") (class "Default")
      (node (ref "E12") (pin "12") (pinfunction "0_12") (pintype "output"))
    )
    (net (code "126") (name "unconnected-(E13A-0-Pad12)") (class "Default")
      (node (ref "E13") (pin "12") (pinfunction "0_12") (pintype "output"))
    )
    (net (code "127") (name "unconnected-(E14A-0-Pad12)") (class "Default")
      (node (ref "E14") (pin "12") (pinfunction "0_12") (pintype "output"))
    )
    (net (code "128") (name "unconnected-(E15A-0-Pad12)") (class "Default")
      (node (ref "E15") (pin "12") (pinfunction "0_12") (pintype "output"))
    )
    (net (code "129") (name "unconnected-(E18A-I2-Pad6)") (class "Default")
      (node (ref "E18") (pin "6") (pinfunction "I2_6") (pintype "input"))
    )
    (net (code "130") (name "unconnected-(E18A-I9-Pad12)") (class "Default")
      (node (ref "E18") (pin "12") (pinfunction "I9_12") (pintype "passive"))
    )
    (net (code "131") (name "unconnected-(E18A-I10-Pad11)") (class "Default")
      (node (ref "E18") (pin "11") (pinfunction "I10_11") (pintype "passive"))
    )
    (net (code "132") (name "unconnected-(E22A-I2-Pad6)") (class "Default")
      (node (ref "E22") (pin "6") (pinfunction "I2_6") (pintype "input"))
    )
    (net (code "133") (name "unconnected-(E22A-I9-Pad12)") (class "Default")
      (node (ref "E22") (pin "12") (pinfunction "I9_12") (pintype "passive"))
    )
    (net (code "134") (name "unconnected-(E22A-I10-Pad11)") (class "Default")
      (node (ref "E22") (pin "11") (pinfunction "I10_11") (pintype "passive"))
    )
    (net (code "135") (name "unconnected-(E23A-0-Pad12)") (class "Default")
      (node (ref "E23") (pin "12") (pinfunction "0_12") (pintype "output"))
    )
    (net (code "136") (name "unconnected-(E24A-0-Pad12)") (class "Default")
      (node (ref "E24") (pin "12") (pinfunction "0_12") (pintype "output"))
    )
    (net (code "137") (name "unconnected-(E25A-0-Pad12)") (class "Default")
      (node (ref "E25") (pin "12") (pinfunction "0_12") (pintype "output"))
    )
    (net (code "138") (name "unconnected-(E26A-0-Pad12)") (class "Default")
      (node (ref "E26") (pin "12") (pinfunction "0_12") (pintype "output"))
    )
    (net (code "139") (name "unconnected-(E29A-0-Pad12)") (class "Default")
      (node (ref "E29") (pin "12") (pinfunction "0_12") (pintype "output"))
    )
    (net (code "140") (name "unconnected-(E30A-0-Pad12)") (class "Default")
      (node (ref "E30") (pin "12") (pinfunction "0_12") (pintype "output"))
    )
    (net (code "141") (name "unconnected-(E31A-0-Pad12)") (class "Default")
      (node (ref "E31") (pin "12") (pinfunction "0_12") (pintype "output"))
    )
    (net (code "142") (name "unconnected-(E32A-0-Pad12)") (class "Default")
      (node (ref "E32") (pin "12") (pinfunction "0_12") (pintype "output"))
    )
  )
)
